# haptic-control.net
KiCad netlist of a schematic drawn in EAGLE
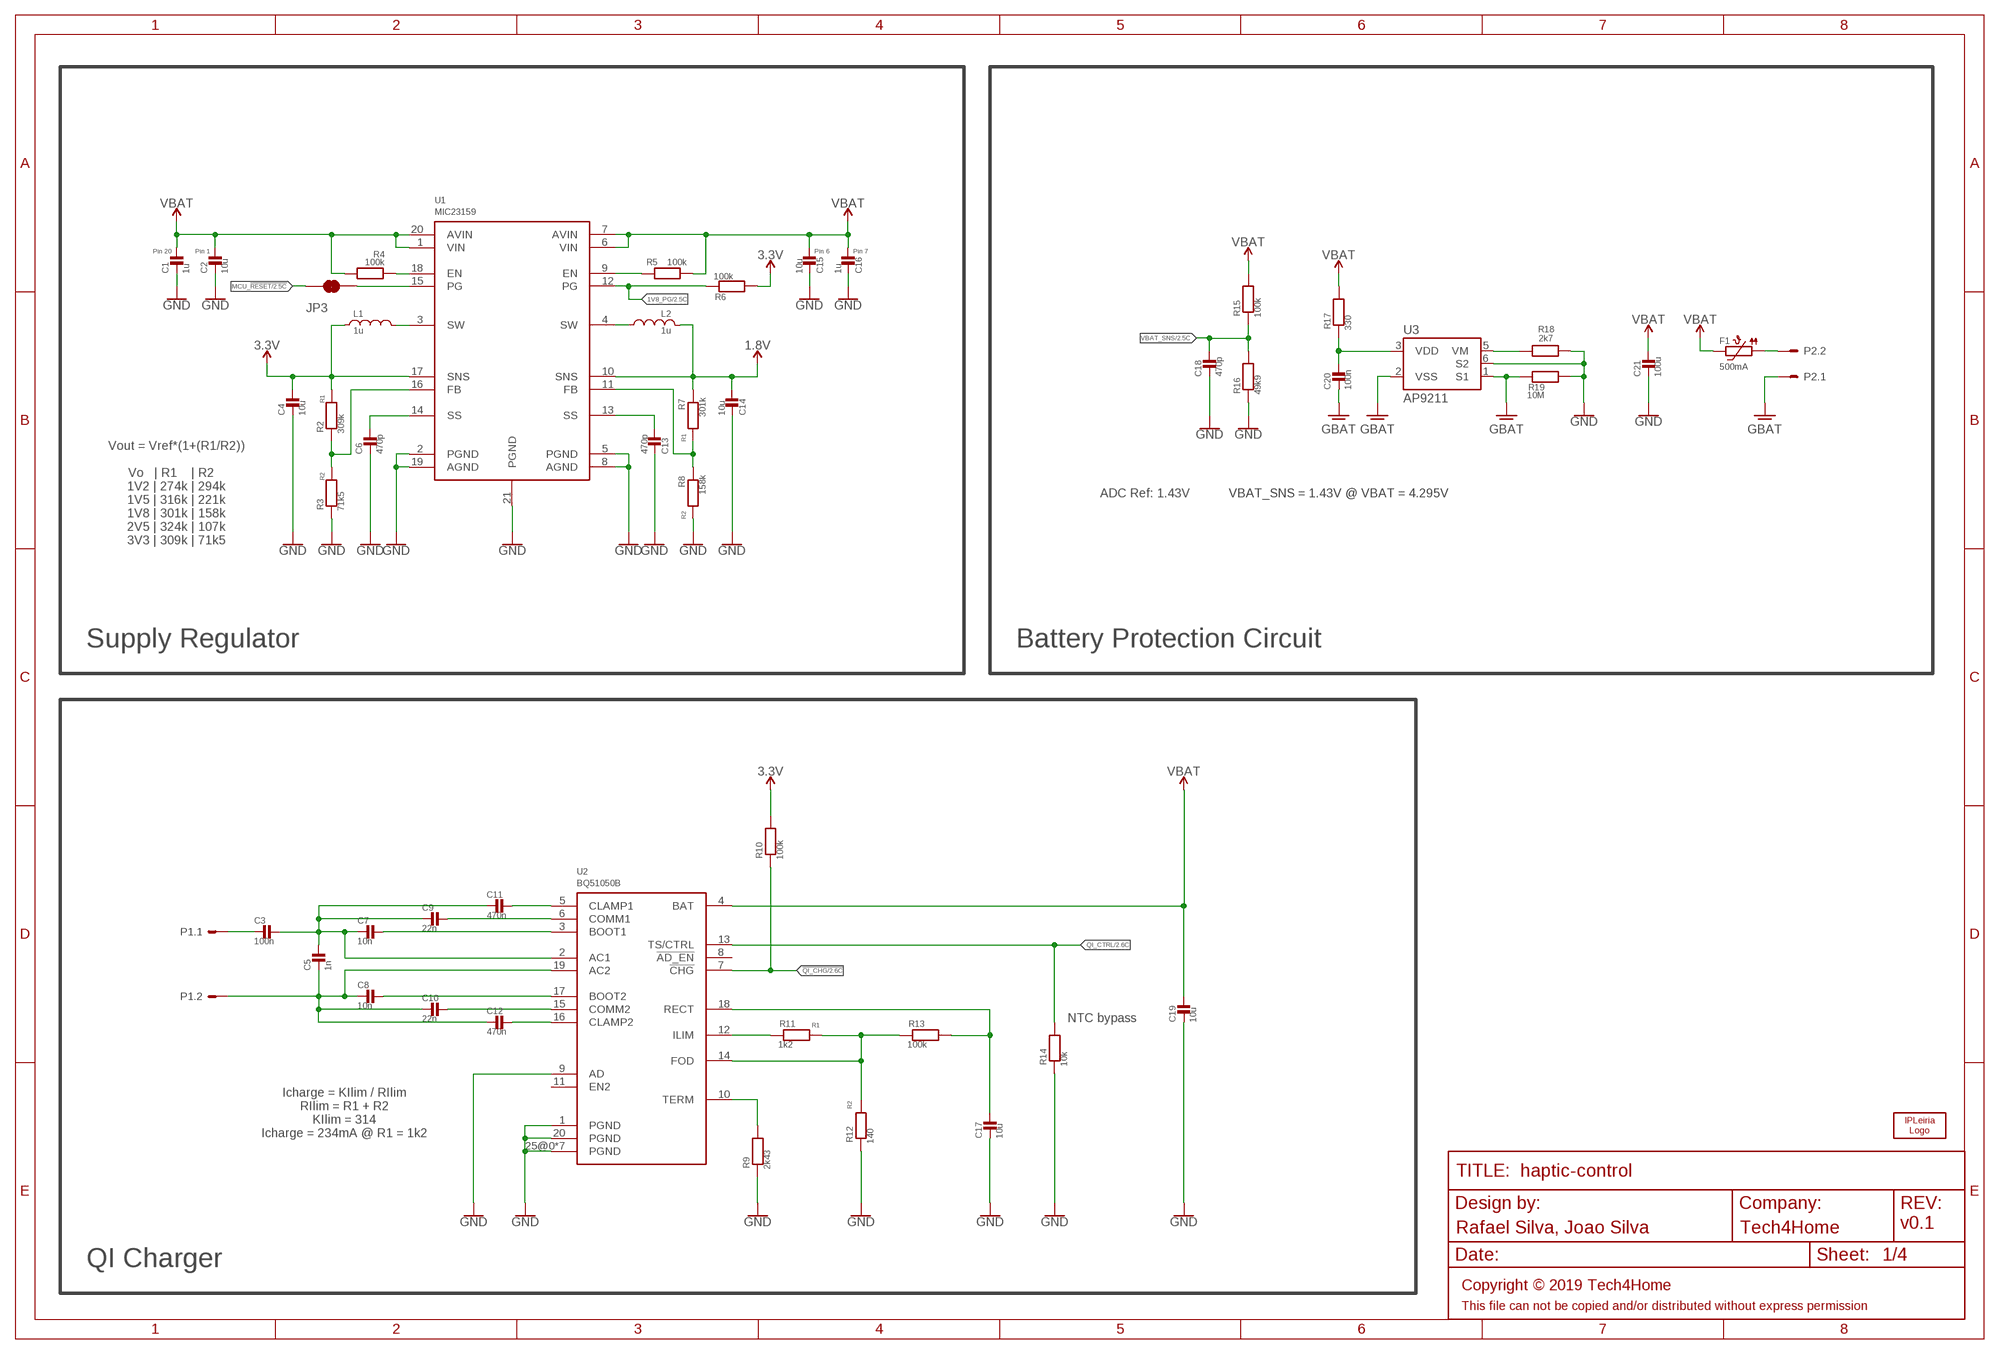
[diagram p0: schematic, sheet 1]
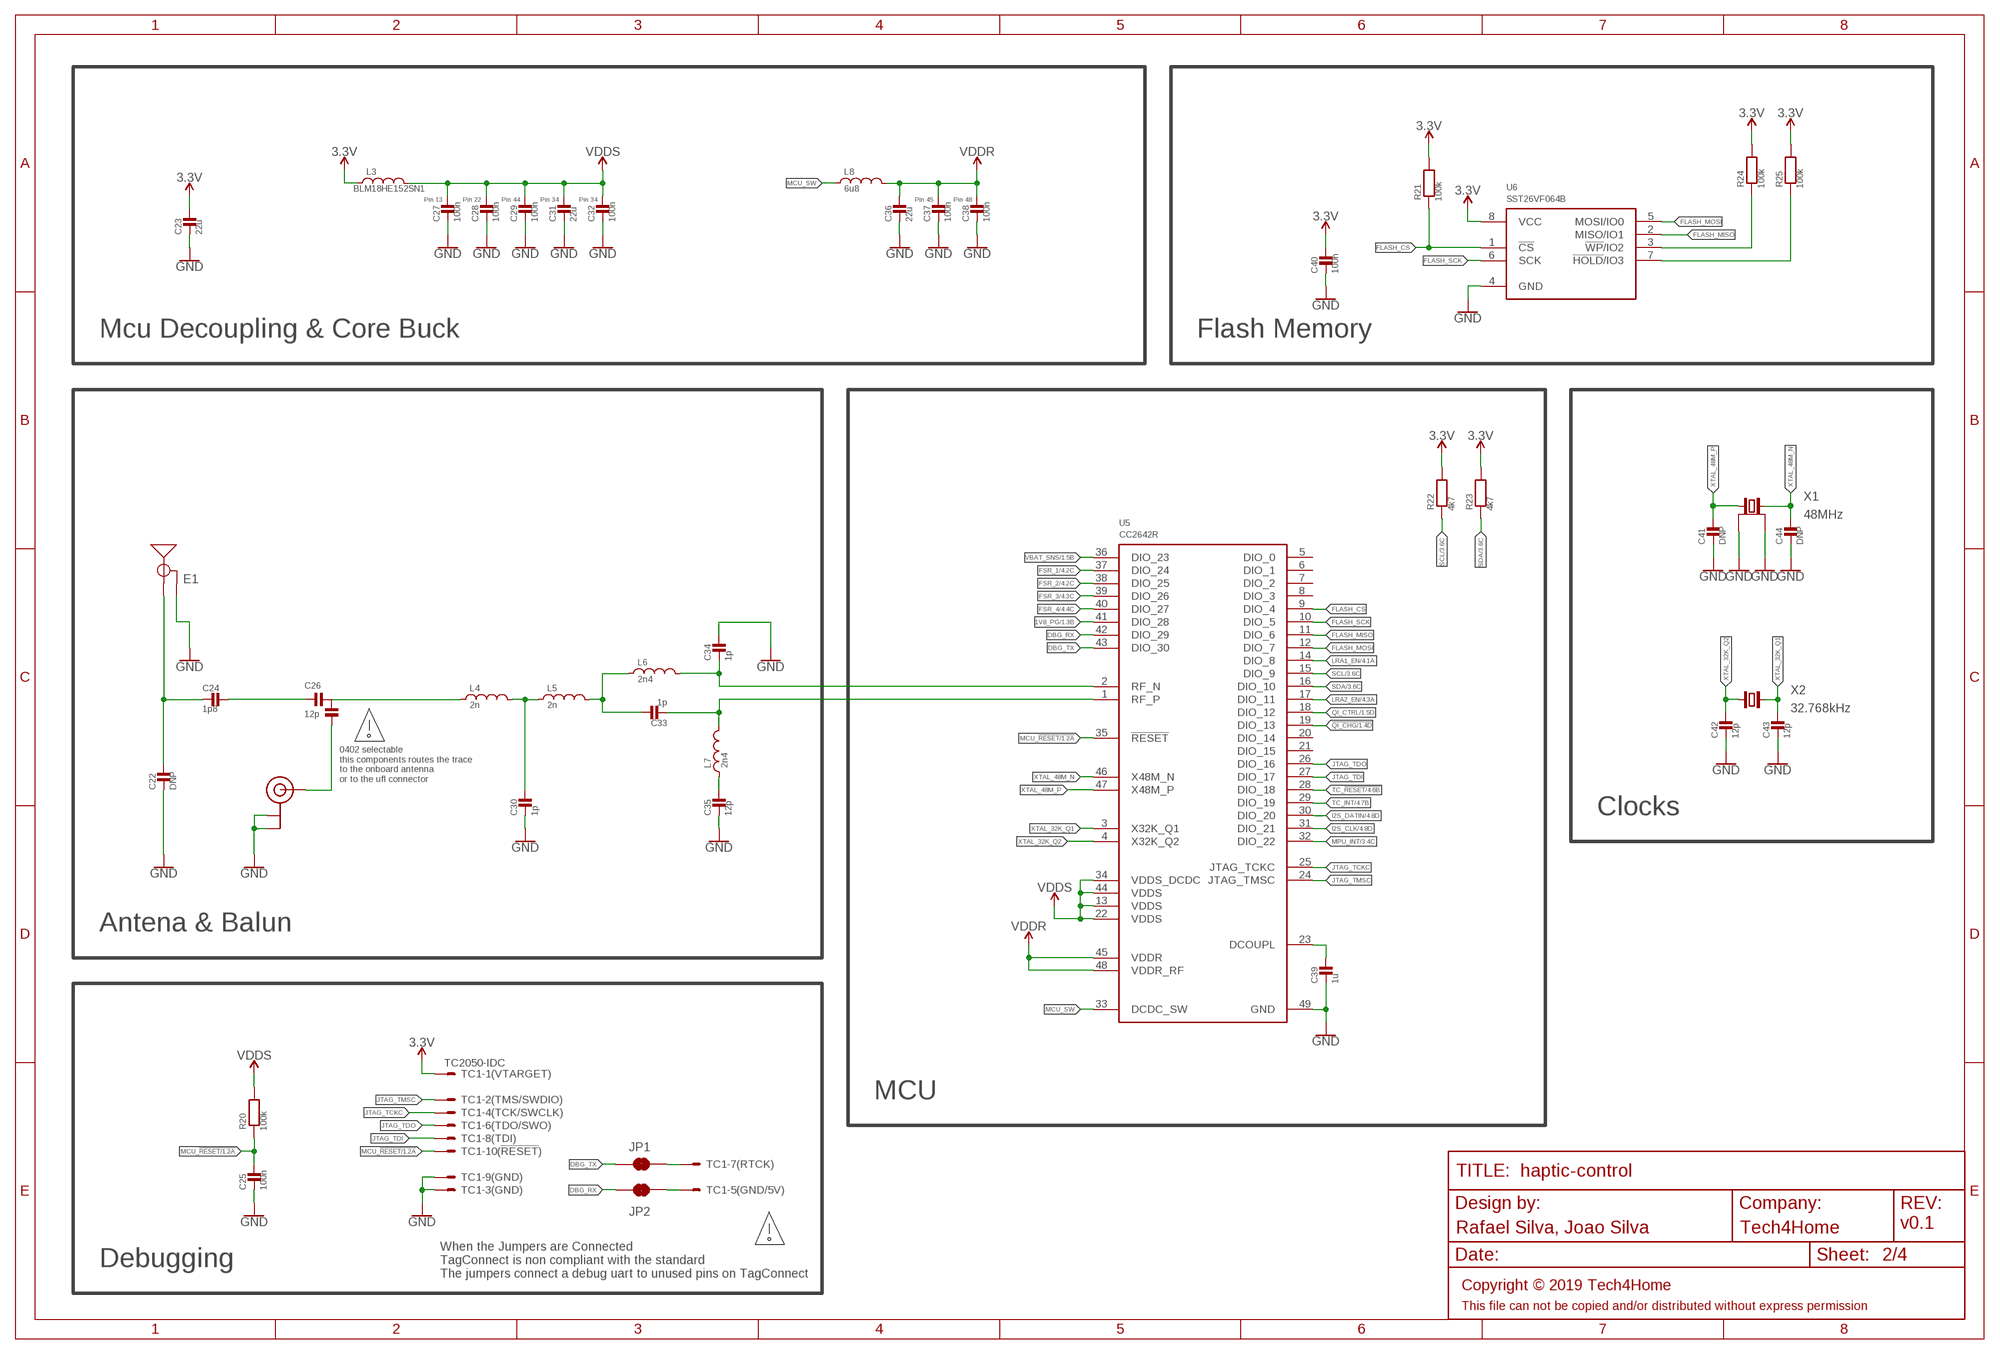
[diagram p1: schematic, sheet 2]
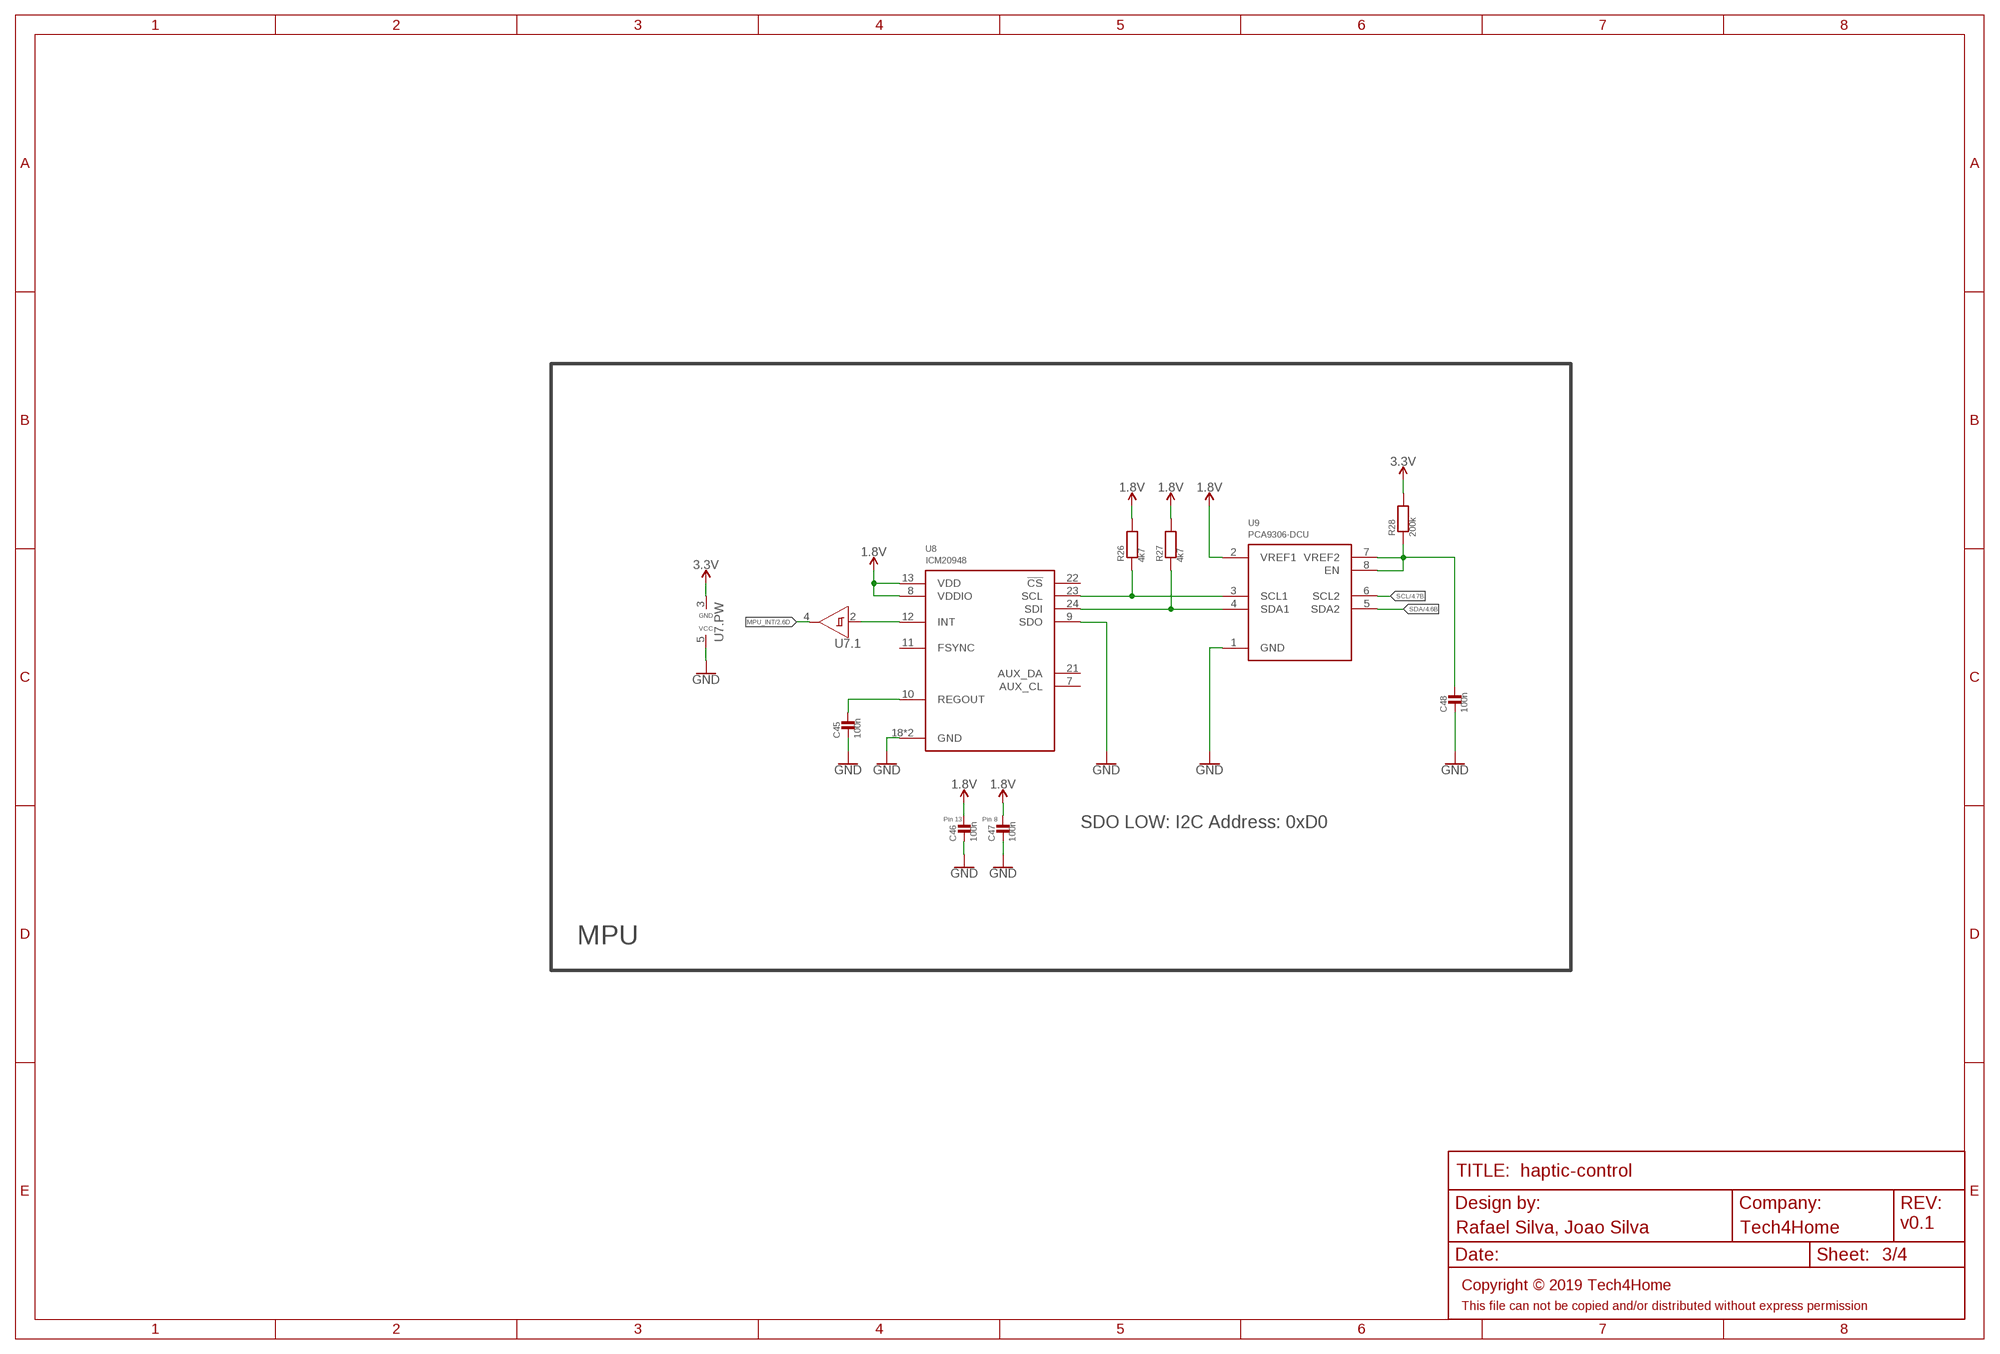
[diagram p2: schematic, sheet 3]
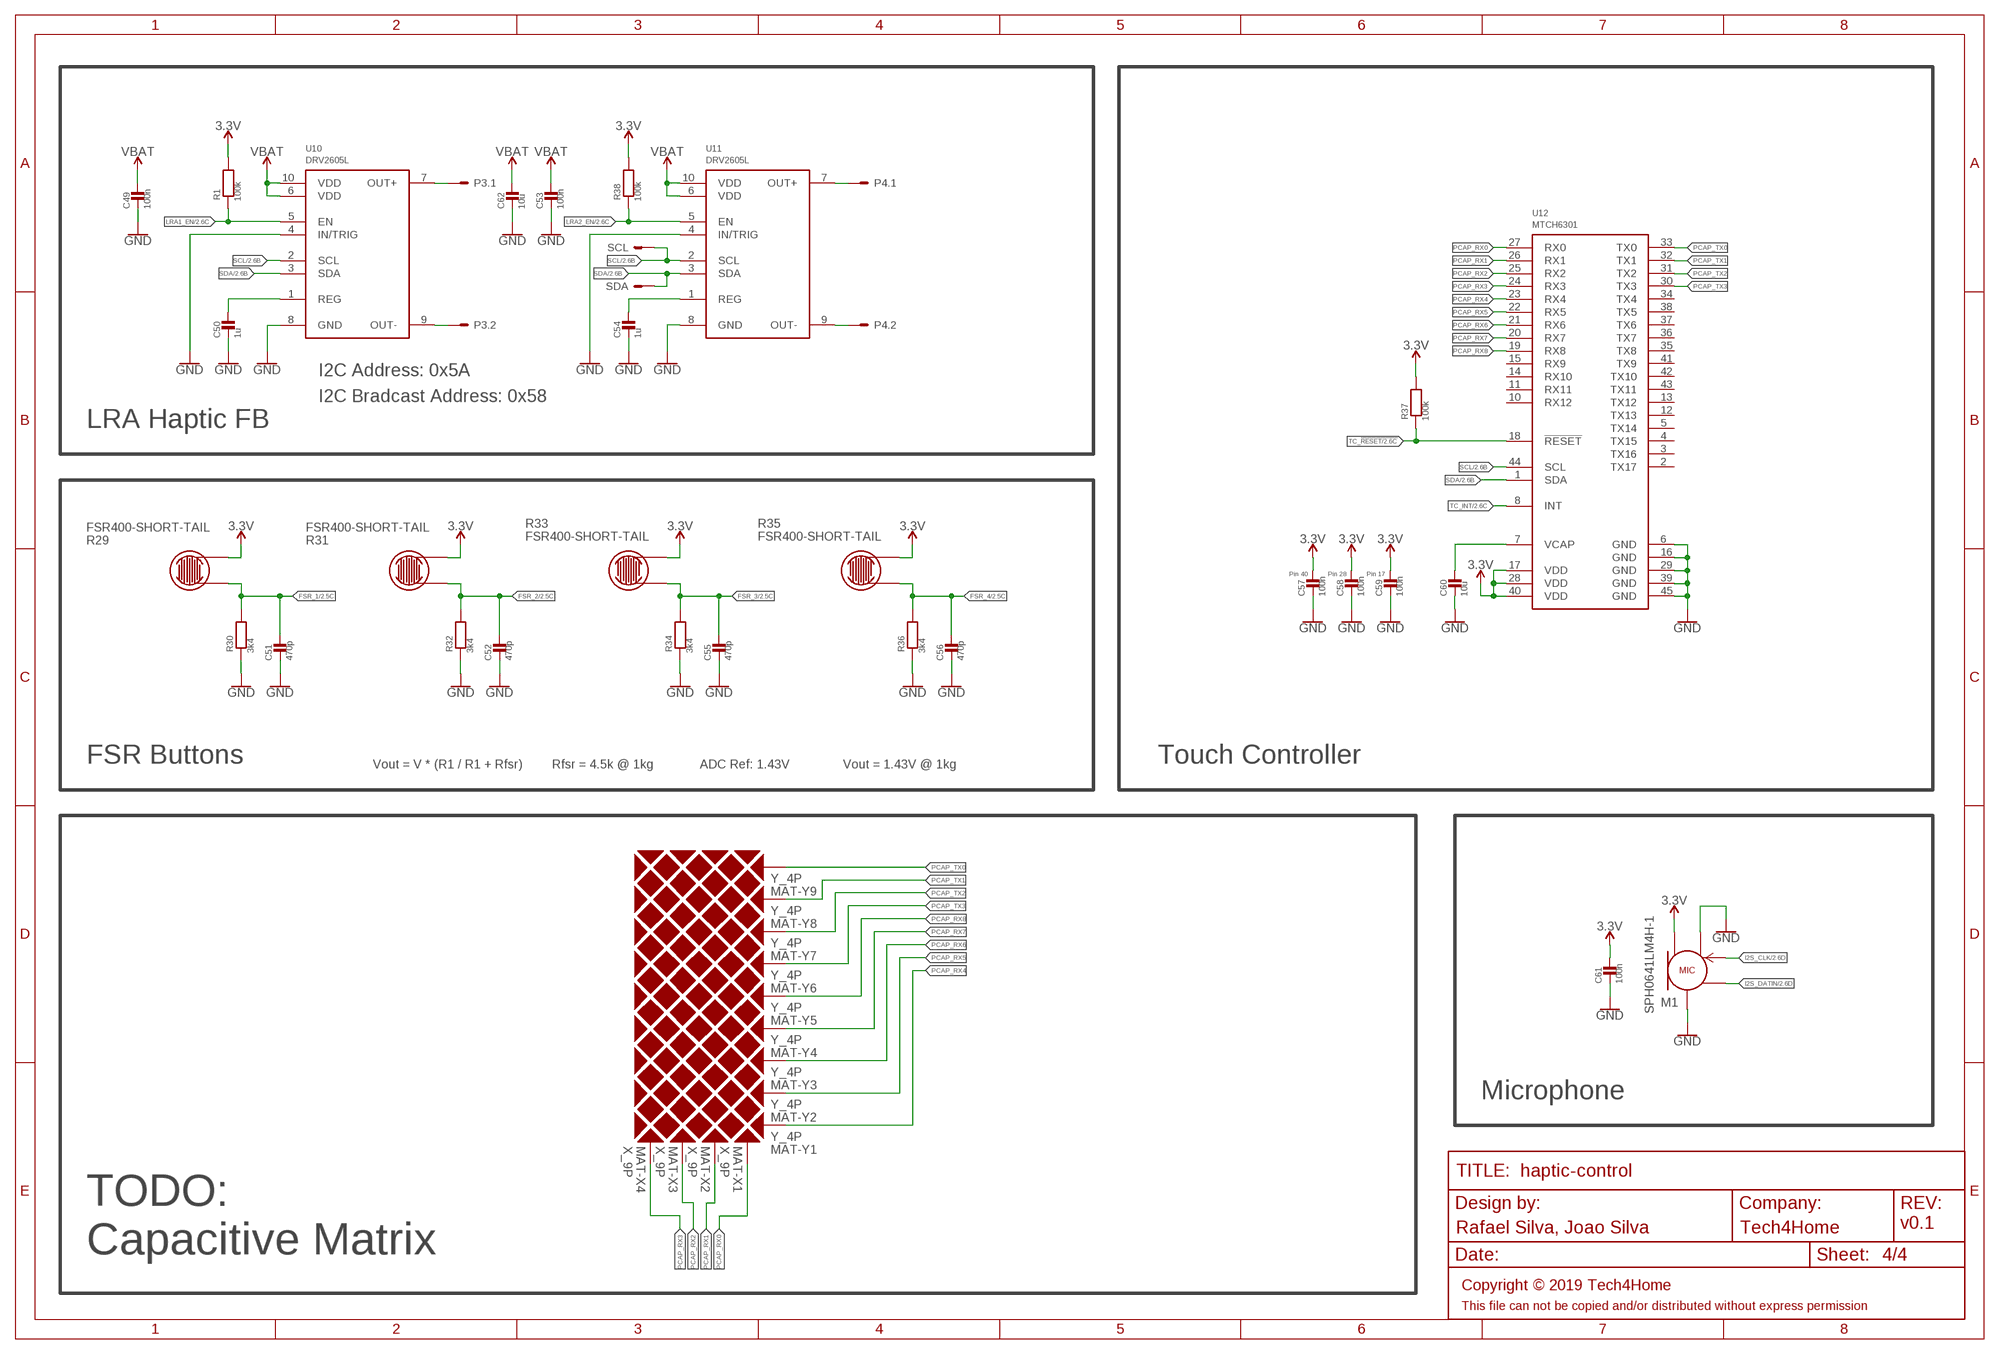
[diagram p3: schematic, sheet 4]

(export (version "E")
  (design (tool "Eeschema 10.0.6"))
  (components
    (comp (ref "C1")
      (value "1u")
      (footprint "eagle-import:0603_WAVE")
      (libsource (lib "eagle-import") (part "MLCC0603"))
    )
    (comp (ref "C2")
      (value "10u")
      (footprint "eagle-import:0603_WAVE")
      (libsource (lib "eagle-import") (part "MLCC0603"))
    )
    (comp (ref "C3")
      (value "100n")
      (footprint "eagle-import:_0402")
      (libsource (lib "eagle-import") (part "MLCC_0402"))
    )
    (comp (ref "C4")
      (value "10u")
      (footprint "eagle-import:0603_WAVE")
      (libsource (lib "eagle-import") (part "MLCC0603"))
    )
    (comp (ref "C5")
      (value "1n")
      (footprint "eagle-import:_0402")
      (libsource (lib "eagle-import") (part "MLCC_0402"))
    )
    (comp (ref "C6")
      (value "470p")
      (footprint "eagle-import:_0402")
      (libsource (lib "eagle-import") (part "MLCC_0402"))
    )
    (comp (ref "C7")
      (value "10n")
      (footprint "eagle-import:_0402")
      (libsource (lib "eagle-import") (part "MLCC_0402"))
    )
    (comp (ref "C8")
      (value "10n")
      (footprint "eagle-import:_0402")
      (libsource (lib "eagle-import") (part "MLCC_0402"))
    )
    (comp (ref "C9")
      (value "22n")
      (footprint "eagle-import:_0402")
      (libsource (lib "eagle-import") (part "MLCC_0402"))
    )
    (comp (ref "C10")
      (value "22n")
      (footprint "eagle-import:_0402")
      (libsource (lib "eagle-import") (part "MLCC_0402"))
    )
    (comp (ref "C11")
      (value "470n")
      (footprint "eagle-import:_0402")
      (libsource (lib "eagle-import") (part "MLCC_0402"))
    )
    (comp (ref "C12")
      (value "470n")
      (footprint "eagle-import:_0402")
      (libsource (lib "eagle-import") (part "MLCC_0402"))
    )
    (comp (ref "C13")
      (value "470p")
      (footprint "eagle-import:_0402")
      (libsource (lib "eagle-import") (part "MLCC_0402"))
    )
    (comp (ref "C14")
      (value "10u")
      (footprint "eagle-import:0603_WAVE")
      (libsource (lib "eagle-import") (part "MLCC0603"))
    )
    (comp (ref "C15")
      (value "10u")
      (footprint "eagle-import:0603_WAVE")
      (libsource (lib "eagle-import") (part "MLCC0603"))
    )
    (comp (ref "C16")
      (value "1u")
      (footprint "eagle-import:0603_WAVE")
      (libsource (lib "eagle-import") (part "MLCC0603"))
    )
    (comp (ref "C17")
      (value "10u")
      (footprint "eagle-import:0603_WAVE")
      (libsource (lib "eagle-import") (part "MLCC0603"))
    )
    (comp (ref "C18")
      (value "470p")
      (footprint "eagle-import:_0402")
      (libsource (lib "eagle-import") (part "MLCC_0402"))
    )
    (comp (ref "C19")
      (value "10u")
      (footprint "eagle-import:0603_WAVE")
      (libsource (lib "eagle-import") (part "MLCC0603"))
    )
    (comp (ref "C20")
      (value "100n")
      (footprint "eagle-import:_0402")
      (libsource (lib "eagle-import") (part "MLCC_0402"))
    )
    (comp (ref "C21")
      (value "100u")
      (footprint "eagle-import:_1206")
      (libsource (lib "eagle-import") (part "MLCC_1206"))
    )
    (comp (ref "F1")
      (value "500mA")
      (footprint "eagle-import:0805")
      (libsource (lib "eagle-import") (part "PTC0805"))
    )
    (comp (ref "JP3")
      (value "JUMPER-SMT_2_NC_TRACE_SILK")
      (footprint "eagle-import:SMT-JUMPER_2_NC_TRACE_SILK")
      (libsource (lib "eagle-import") (part "JUMPER-SMT_2_NC_TRACE_SILK"))
    )
    (comp (ref "L1")
      (value "1u")
      (footprint "eagle-import:_0806")
      (libsource (lib "eagle-import") (part "INDUCTOR_NC_0806"))
    )
    (comp (ref "L2")
      (value "1u")
      (footprint "eagle-import:_0806")
      (libsource (lib "eagle-import") (part "INDUCTOR_NC_0806"))
    )
    (comp (ref "LOGO1")
      (value "IPL-10MM")
      (footprint "eagle-import:IPL_10MM")
      (libsource (lib "eagle-import") (part "IPL-10MM"))
    )
    (comp (ref "P1")
      (value "2P-PAD_1X3.5")
      (footprint "eagle-import:PAD1X3_5MM-2P")
      (libsource (lib "eagle-import") (part "2P-PAD_1X3.5"))
    )
    (comp (ref "P2")
      (value "2P-PAD_1X3.5")
      (footprint "eagle-import:PAD1X3_5MM-2P")
      (libsource (lib "eagle-import") (part "2P-PAD_1X3.5"))
    )
    (comp (ref "R2")
      (value "309k")
      (footprint "eagle-import:_0402")
      (libsource (lib "eagle-import") (part "RESISTOR_0402"))
    )
    (comp (ref "R3")
      (value "71k5")
      (footprint "eagle-import:_0402")
      (libsource (lib "eagle-import") (part "RESISTOR_0402"))
    )
    (comp (ref "R4")
      (value "100k")
      (footprint "eagle-import:_0402")
      (libsource (lib "eagle-import") (part "RESISTOR_0402"))
    )
    (comp (ref "R5")
      (value "100k")
      (footprint "eagle-import:_0402")
      (libsource (lib "eagle-import") (part "RESISTOR_0402"))
    )
    (comp (ref "R6")
      (value "100k")
      (footprint "eagle-import:_0402")
      (libsource (lib "eagle-import") (part "RESISTOR_0402"))
    )
    (comp (ref "R7")
      (value "301k")
      (footprint "eagle-import:_0402")
      (libsource (lib "eagle-import") (part "RESISTOR_0402"))
    )
    (comp (ref "R8")
      (value "158k")
      (footprint "eagle-import:_0402")
      (libsource (lib "eagle-import") (part "RESISTOR_0402"))
    )
    (comp (ref "R9")
      (value "2k43")
      (footprint "eagle-import:_0402")
      (libsource (lib "eagle-import") (part "RESISTOR_0402"))
    )
    (comp (ref "R10")
      (value "100k")
      (footprint "eagle-import:_0402")
      (libsource (lib "eagle-import") (part "RESISTOR_0402"))
    )
    (comp (ref "R11")
      (value "1k2")
      (footprint "eagle-import:_0402")
      (libsource (lib "eagle-import") (part "RESISTOR_0402"))
    )
    (comp (ref "R12")
      (value "140")
      (footprint "eagle-import:_0402")
      (libsource (lib "eagle-import") (part "RESISTOR_0402"))
    )
    (comp (ref "R13")
      (value "100k")
      (footprint "eagle-import:_0402")
      (libsource (lib "eagle-import") (part "RESISTOR_0402"))
    )
    (comp (ref "R14")
      (value "10k")
      (footprint "eagle-import:_0402")
      (libsource (lib "eagle-import") (part "RESISTOR_0402"))
    )
    (comp (ref "R15")
      (value "100k")
      (footprint "eagle-import:_0402")
      (libsource (lib "eagle-import") (part "RESISTOR_0402"))
    )
    (comp (ref "R16")
      (value "49k9")
      (footprint "eagle-import:_0402")
      (libsource (lib "eagle-import") (part "RESISTOR_0402"))
    )
    (comp (ref "R17")
      (value "330")
      (footprint "eagle-import:_0402")
      (libsource (lib "eagle-import") (part "RESISTOR_0402"))
    )
    (comp (ref "R18")
      (value "2k7")
      (footprint "eagle-import:_0402")
      (libsource (lib "eagle-import") (part "RESISTOR_0402"))
    )
    (comp (ref "R19")
      (value "10M")
      (footprint "eagle-import:_0402")
      (libsource (lib "eagle-import") (part "RESISTOR_0402"))
    )
    (comp (ref "U1")
      (value "MIC23159")
      (footprint "eagle-import:VQFN20")
      (libsource (lib "eagle-import") (part "MIC23159"))
    )
    (comp (ref "U2")
      (value "BQ51050B")
      (footprint "eagle-import:VQFN20")
      (libsource (lib "eagle-import") (part "BQ51050B"))
    )
    (comp (ref "U3")
      (value "AP9211")
      (footprint "eagle-import:DFN2030-6")
      (libsource (lib "eagle-import") (part "AP9211"))
    )
    (comp (ref "C49")
      (value "100n")
      (footprint "eagle-import:_0402")
      (libsource (lib "eagle-import") (part "MLCC_0402"))
    )
    (comp (ref "C50")
      (value "1u")
      (footprint "eagle-import:0603_WAVE")
      (libsource (lib "eagle-import") (part "MLCC0603"))
    )
    (comp (ref "C51")
      (value "470p")
      (footprint "eagle-import:_0402")
      (libsource (lib "eagle-import") (part "MLCC_0402"))
    )
    (comp (ref "C52")
      (value "470p")
      (footprint "eagle-import:_0402")
      (libsource (lib "eagle-import") (part "MLCC_0402"))
    )
    (comp (ref "C53")
      (value "100n")
      (footprint "eagle-import:_0402")
      (libsource (lib "eagle-import") (part "MLCC_0402"))
    )
    (comp (ref "C54")
      (value "1u")
      (footprint "eagle-import:0603_WAVE")
      (libsource (lib "eagle-import") (part "MLCC0603"))
    )
    (comp (ref "C55")
      (value "470p")
      (footprint "eagle-import:_0402")
      (libsource (lib "eagle-import") (part "MLCC_0402"))
    )
    (comp (ref "C56")
      (value "470p")
      (footprint "eagle-import:_0402")
      (libsource (lib "eagle-import") (part "MLCC_0402"))
    )
    (comp (ref "C57")
      (value "100n")
      (footprint "eagle-import:_0402")
      (libsource (lib "eagle-import") (part "MLCC_0402"))
    )
    (comp (ref "C58")
      (value "100n")
      (footprint "eagle-import:_0402")
      (libsource (lib "eagle-import") (part "MLCC_0402"))
    )
    (comp (ref "C59")
      (value "100n")
      (footprint "eagle-import:_0402")
      (libsource (lib "eagle-import") (part "MLCC_0402"))
    )
    (comp (ref "C60")
      (value "10u")
      (footprint "eagle-import:0603_WAVE")
      (libsource (lib "eagle-import") (part "MLCC0603"))
    )
    (comp (ref "C61")
      (value "100n")
      (footprint "eagle-import:_0402")
      (libsource (lib "eagle-import") (part "MLCC_0402"))
    )
    (comp (ref "C62")
      (value "10u")
      (footprint "eagle-import:0603_WAVE")
      (libsource (lib "eagle-import") (part "MLCC0603"))
    )
    (comp (ref "M1")
      (value "SPH0641LM4H-1")
      (footprint "eagle-import:SPH0641LM4H-1")
      (libsource (lib "eagle-import") (part "SPH0641LM4H-1"))
    )
    (comp (ref "MAT-X1")
      (value "X_9P")
      (footprint "eagle-import:TOUCH_X_9P")
      (libsource (lib "eagle-import") (part "X_9P"))
    )
    (comp (ref "MAT-X2")
      (value "X_9P")
      (footprint "eagle-import:TOUCH_X_9P")
      (libsource (lib "eagle-import") (part "X_9P"))
    )
    (comp (ref "MAT-X3")
      (value "X_9P")
      (footprint "eagle-import:TOUCH_X_9P")
      (libsource (lib "eagle-import") (part "X_9P"))
    )
    (comp (ref "MAT-X4")
      (value "X_9P")
      (footprint "eagle-import:TOUCH_X_9P")
      (libsource (lib "eagle-import") (part "X_9P"))
    )
    (comp (ref "MAT-Y1")
      (value "Y_4P")
      (footprint "eagle-import:TOUCH_Y_4P")
      (libsource (lib "eagle-import") (part "Y_4P"))
    )
    (comp (ref "MAT-Y2")
      (value "Y_4P")
      (footprint "eagle-import:TOUCH_Y_4P")
      (libsource (lib "eagle-import") (part "Y_4P"))
    )
    (comp (ref "MAT-Y3")
      (value "Y_4P")
      (footprint "eagle-import:TOUCH_Y_4P")
      (libsource (lib "eagle-import") (part "Y_4P"))
    )
    (comp (ref "MAT-Y4")
      (value "Y_4P")
      (footprint "eagle-import:TOUCH_Y_4P")
      (libsource (lib "eagle-import") (part "Y_4P"))
    )
    (comp (ref "MAT-Y5")
      (value "Y_4P")
      (footprint "eagle-import:TOUCH_Y_4P")
      (libsource (lib "eagle-import") (part "Y_4P"))
    )
    (comp (ref "MAT-Y6")
      (value "Y_4P")
      (footprint "eagle-import:TOUCH_Y_4P")
      (libsource (lib "eagle-import") (part "Y_4P"))
    )
    (comp (ref "MAT-Y7")
      (value "Y_4P")
      (footprint "eagle-import:TOUCH_Y_4P")
      (libsource (lib "eagle-import") (part "Y_4P"))
    )
    (comp (ref "MAT-Y8")
      (value "Y_4P")
      (footprint "eagle-import:TOUCH_Y_4P")
      (libsource (lib "eagle-import") (part "Y_4P"))
    )
    (comp (ref "MAT-Y9")
      (value "Y_4P")
      (footprint "eagle-import:TOUCH_Y_4P")
      (libsource (lib "eagle-import") (part "Y_4P"))
    )
    (comp (ref "P3")
      (value "2P-PAD_1X3.5")
      (footprint "eagle-import:PAD1X3_5MM-2P")
      (libsource (lib "eagle-import") (part "2P-PAD_1X3.5"))
    )
    (comp (ref "P4")
      (value "2P-PAD_1X3.5")
      (footprint "eagle-import:PAD1X3_5MM-2P")
      (libsource (lib "eagle-import") (part "2P-PAD_1X3.5"))
    )
    (comp (ref "R1")
      (value "100k")
      (footprint "eagle-import:_0402")
      (libsource (lib "eagle-import") (part "RESISTOR_0402"))
    )
    (comp (ref "R29")
      (value "FSR400-SHORT-TAIL")
      (footprint "eagle-import:FSR400-SHORT-TAIL")
      (libsource (lib "eagle-import") (part "FSR400-SHORT-TAIL"))
    )
    (comp (ref "R30")
      (value "3k4")
      (footprint "eagle-import:_0402")
      (libsource (lib "eagle-import") (part "RESISTOR_0402"))
    )
    (comp (ref "R31")
      (value "FSR400-SHORT-TAIL")
      (footprint "eagle-import:FSR400-SHORT-TAIL")
      (libsource (lib "eagle-import") (part "FSR400-SHORT-TAIL"))
    )
    (comp (ref "R32")
      (value "3k4")
      (footprint "eagle-import:_0402")
      (libsource (lib "eagle-import") (part "RESISTOR_0402"))
    )
    (comp (ref "R33")
      (value "FSR400-SHORT-TAIL")
      (footprint "eagle-import:FSR400-SHORT-TAIL")
      (libsource (lib "eagle-import") (part "FSR400-SHORT-TAIL"))
    )
    (comp (ref "R34")
      (value "3k4")
      (footprint "eagle-import:_0402")
      (libsource (lib "eagle-import") (part "RESISTOR_0402"))
    )
    (comp (ref "R35")
      (value "FSR400-SHORT-TAIL")
      (footprint "eagle-import:FSR400-SHORT-TAIL")
      (libsource (lib "eagle-import") (part "FSR400-SHORT-TAIL"))
    )
    (comp (ref "R36")
      (value "3k4")
      (footprint "eagle-import:_0402")
      (libsource (lib "eagle-import") (part "RESISTOR_0402"))
    )
    (comp (ref "R37")
      (value "100k")
      (footprint "eagle-import:_0402")
      (libsource (lib "eagle-import") (part "RESISTOR_0402"))
    )
    (comp (ref "R38")
      (value "100k")
      (footprint "eagle-import:_0402")
      (libsource (lib "eagle-import") (part "RESISTOR_0402"))
    )
    (comp (ref "SCL")
      (value "TEST_POINT")
      (footprint "eagle-import:TEST_POINT")
      (libsource (lib "eagle-import") (part "TEST_POINT"))
    )
    (comp (ref "SDA")
      (value "TEST_POINT")
      (footprint "eagle-import:TEST_POINT")
      (libsource (lib "eagle-import") (part "TEST_POINT"))
    )
    (comp (ref "U10")
      (value "DRV2605L")
      (footprint "eagle-import:VSSOP10")
      (libsource (lib "eagle-import") (part "DRV2605L"))
    )
    (comp (ref "U11")
      (value "DRV2605L")
      (footprint "eagle-import:VSSOP10")
      (libsource (lib "eagle-import") (part "DRV2605L"))
    )
    (comp (ref "U12")
      (value "MTCH6301")
      (footprint "eagle-import:QFN44")
      (libsource (lib "eagle-import") (part "MTCH6301"))
    )
    (comp (ref "C45")
      (value "100n")
      (footprint "eagle-import:_0402")
      (libsource (lib "eagle-import") (part "MLCC_0402"))
    )
    (comp (ref "C46")
      (value "100n")
      (footprint "eagle-import:_0402")
      (libsource (lib "eagle-import") (part "MLCC_0402"))
    )
    (comp (ref "C47")
      (value "100n")
      (footprint "eagle-import:_0402")
      (libsource (lib "eagle-import") (part "MLCC_0402"))
    )
    (comp (ref "C48")
      (value "100n")
      (footprint "eagle-import:_0402")
      (libsource (lib "eagle-import") (part "MLCC_0402"))
    )
    (comp (ref "R26")
      (value "4k7")
      (footprint "eagle-import:_0402")
      (libsource (lib "eagle-import") (part "RESISTOR_0402"))
    )
    (comp (ref "R27")
      (value "4k7")
      (footprint "eagle-import:_0402")
      (libsource (lib "eagle-import") (part "RESISTOR_0402"))
    )
    (comp (ref "R28")
      (value "200k")
      (footprint "eagle-import:_0402")
      (libsource (lib "eagle-import") (part "RESISTOR_0402"))
    )
    (comp (ref "U7")
      (value "74LVC1G17")
      (footprint "eagle-import:SC70-5")
      (libsource (lib "eagle-import") (part "74LVC1G17"))
    )
    (comp (ref "U8")
      (value "ICM20948")
      (footprint "eagle-import:QFN20")
      (libsource (lib "eagle-import") (part "ICM20948"))
    )
    (comp (ref "U9")
      (value "PCA9306-DCU")
      (footprint "eagle-import:VSSOP8")
      (libsource (lib "eagle-import") (part "PCA9306-DCU"))
    )
    (comp (ref "A1")
      (value "U.FL")
      (footprint "eagle-import:U.FL")
      (libsource (lib "eagle-import") (part "U.FL"))
    )
    (comp (ref "C22")
      (value "DNP")
      (footprint "eagle-import:_0402")
      (libsource (lib "eagle-import") (part "MLCC_0402"))
    )
    (comp (ref "C23")
      (value "22u")
      (footprint "eagle-import:0603_WAVE")
      (libsource (lib "eagle-import") (part "MLCC0603"))
    )
    (comp (ref "C24")
      (value "1p8")
      (footprint "eagle-import:_0402")
      (libsource (lib "eagle-import") (part "MLCC_0402"))
    )
    (comp (ref "C25")
      (value "100n")
      (footprint "eagle-import:_0402")
      (libsource (lib "eagle-import") (part "MLCC_0402"))
    )
    (comp (ref "C26")
      (value "12p")
      (footprint "eagle-import:_0402_SEL")
      (libsource (lib "eagle-import") (part "MLCC_SEL"))
    )
    (comp (ref "C27")
      (value "100n")
      (footprint "eagle-import:_0402")
      (libsource (lib "eagle-import") (part "MLCC_0402"))
    )
    (comp (ref "C28")
      (value "100n")
      (footprint "eagle-import:_0402")
      (libsource (lib "eagle-import") (part "MLCC_0402"))
    )
    (comp (ref "C29")
      (value "100n")
      (footprint "eagle-import:_0402")
      (libsource (lib "eagle-import") (part "MLCC_0402"))
    )
    (comp (ref "C30")
      (value "1p")
      (footprint "eagle-import:_0402")
      (libsource (lib "eagle-import") (part "MLCC_0402"))
    )
    (comp (ref "C31")
      (value "22u")
      (footprint "eagle-import:0603_WAVE")
      (libsource (lib "eagle-import") (part "MLCC0603"))
    )
    (comp (ref "C32")
      (value "100n")
      (footprint "eagle-import:_0402")
      (libsource (lib "eagle-import") (part "MLCC_0402"))
    )
    (comp (ref "C33")
      (value "1p")
      (footprint "eagle-import:_0402")
      (libsource (lib "eagle-import") (part "MLCC_0402"))
    )
    (comp (ref "C34")
      (value "1p")
      (footprint "eagle-import:_0402")
      (libsource (lib "eagle-import") (part "MLCC_0402"))
    )
    (comp (ref "C35")
      (value "12p")
      (footprint "eagle-import:_0402")
      (libsource (lib "eagle-import") (part "MLCC_0402"))
    )
    (comp (ref "C36")
      (value "22u")
      (footprint "eagle-import:0603_WAVE")
      (libsource (lib "eagle-import") (part "MLCC0603"))
    )
    (comp (ref "C37")
      (value "100n")
      (footprint "eagle-import:_0402")
      (libsource (lib "eagle-import") (part "MLCC_0402"))
    )
    (comp (ref "C38")
      (value "100n")
      (footprint "eagle-import:_0402")
      (libsource (lib "eagle-import") (part "MLCC_0402"))
    )
    (comp (ref "C39")
      (value "1u")
      (footprint "eagle-import:0603_WAVE")
      (libsource (lib "eagle-import") (part "MLCC0603"))
    )
    (comp (ref "C40")
      (value "100n")
      (footprint "eagle-import:_0402")
      (libsource (lib "eagle-import") (part "MLCC_0402"))
    )
    (comp (ref "C41")
      (value "DNP")
      (footprint "eagle-import:_0402")
      (libsource (lib "eagle-import") (part "MLCC_0402"))
    )
    (comp (ref "C42")
      (value "12p")
      (footprint "eagle-import:_0402")
      (libsource (lib "eagle-import") (part "MLCC_0402"))
    )
    (comp (ref "C43")
      (value "12p")
      (footprint "eagle-import:_0402")
      (libsource (lib "eagle-import") (part "MLCC_0402"))
    )
    (comp (ref "C44")
      (value "DNP")
      (footprint "eagle-import:_0402")
      (libsource (lib "eagle-import") (part "MLCC_0402"))
    )
    (comp (ref "E1")
      (value "2.4GHZTRACE-15.2MM")
      (footprint "eagle-import:TRACE_ANTENNA_2.4GHZ_15.2MM")
      (libsource (lib "eagle-import") (part "2.4GHZTRACE-15.2MM"))
    )
    (comp (ref "JP1")
      (value "JUMPER-SMT_2_NC_TRACE_SILK")
      (footprint "eagle-import:SMT-JUMPER_2_NC_TRACE_SILK")
      (libsource (lib "eagle-import") (part "JUMPER-SMT_2_NC_TRACE_SILK"))
    )
    (comp (ref "JP2")
      (value "JUMPER-SMT_2_NC_TRACE_SILK")
      (footprint "eagle-import:SMT-JUMPER_2_NC_TRACE_SILK")
      (libsource (lib "eagle-import") (part "JUMPER-SMT_2_NC_TRACE_SILK"))
    )
    (comp (ref "L3")
      (value "BLM18HE152SN1")
      (footprint "eagle-import:_0603")
      (libsource (lib "eagle-import") (part "INDUCTOR_NC_0603"))
    )
    (comp (ref "L4")
      (value "2n")
      (footprint "eagle-import:_0402")
      (libsource (lib "eagle-import") (part "INDUCTOR_NC_0402"))
    )
    (comp (ref "L5")
      (value "2n")
      (footprint "eagle-import:_0402")
      (libsource (lib "eagle-import") (part "INDUCTOR_NC_0402"))
    )
    (comp (ref "L6")
      (value "2n4")
      (footprint "eagle-import:_0402")
      (libsource (lib "eagle-import") (part "INDUCTOR_NC_0402"))
    )
    (comp (ref "L7")
      (value "2n4")
      (footprint "eagle-import:_0402")
      (libsource (lib "eagle-import") (part "INDUCTOR_NC_0402"))
    )
    (comp (ref "L8")
      (value "6u8")
      (footprint "eagle-import:_0806")
      (libsource (lib "eagle-import") (part "INDUCTOR_NC_0806"))
    )
    (comp (ref "R20")
      (value "100k")
      (footprint "eagle-import:_0402")
      (libsource (lib "eagle-import") (part "RESISTOR_0402"))
    )
    (comp (ref "R21")
      (value "100k")
      (footprint "eagle-import:_0402")
      (libsource (lib "eagle-import") (part "RESISTOR_0402"))
    )
    (comp (ref "R22")
      (value "4k7")
      (footprint "eagle-import:_0402")
      (libsource (lib "eagle-import") (part "RESISTOR_0402"))
    )
    (comp (ref "R23")
      (value "4k7")
      (footprint "eagle-import:_0402")
      (libsource (lib "eagle-import") (part "RESISTOR_0402"))
    )
    (comp (ref "R24")
      (value "100k")
      (footprint "eagle-import:_0402")
      (libsource (lib "eagle-import") (part "RESISTOR_0402"))
    )
    (comp (ref "R25")
      (value "100k")
      (footprint "eagle-import:_0402")
      (libsource (lib "eagle-import") (part "RESISTOR_0402"))
    )
    (comp (ref "TC1")
      (value "TC2050-IDC")
      (footprint "eagle-import:TC2050-IDC")
      (libsource (lib "eagle-import") (part "TC2050-IDC"))
    )
    (comp (ref "U5")
      (value "CC2642R")
      (footprint "eagle-import:QFN48")
      (libsource (lib "eagle-import") (part "CC2642R"))
    )
    (comp (ref "U6")
      (value "SST26VF064B")
      (footprint "eagle-import:WSOIC8")
      (libsource (lib "eagle-import") (part "SST26VF064B"))
    )
    (comp (ref "X1")
      (value "48MHz")
      (footprint "eagle-import:4-SMD-3225")
      (libsource (lib "eagle-import") (part "CRYSTAL_4P"))
    )
    (comp (ref "X2")
      (value "32.768kHz")
      (footprint "eagle-import:2-SMD-3215")
      (libsource (lib "eagle-import") (part "CRYSTAL2-SMD-3215"))
    )
  )
  (nets
    (net (code "1") (name "1.8V") (class "Default")
      (node (ref "C14") (pin "P$1") (pinfunction "P$1_P$1") (pintype "bidirectional"))
      (node (ref "C46") (pin "1") (pinfunction "P$1_1") (pintype "bidirectional"))
      (node (ref "C47") (pin "1") (pinfunction "P$1_1") (pintype "bidirectional"))
      (node (ref "L2") (pin "1") (pinfunction "P$1_1") (pintype "bidirectional"))
      (node (ref "R26") (pin "2") (pinfunction "P$2_2") (pintype "bidirectional"))
      (node (ref "R27") (pin "2") (pinfunction "P$2_2") (pintype "bidirectional"))
      (node (ref "R7") (pin "1") (pinfunction "P$1_1") (pintype "bidirectional"))
      (node (ref "U1") (pin "10") (pinfunction "SNS_10") (pintype "bidirectional"))
      (node (ref "U8") (pin "13") (pinfunction "VDD_13") (pintype "bidirectional"))
      (node (ref "U8") (pin "8") (pinfunction "VDDIO_8") (pintype "bidirectional"))
      (node (ref "U9") (pin "2") (pinfunction "VREF1_2") (pintype "bidirectional"))
    )
    (net (code "2") (name "1V8_PG") (class "Default")
      (node (ref "R6") (pin "1") (pinfunction "P$1_1") (pintype "bidirectional"))
      (node (ref "U1") (pin "12") (pinfunction "PG_12") (pintype "bidirectional"))
      (node (ref "U5") (pin "41") (pinfunction "DIO_28_41") (pintype "bidirectional"))
    )
    (net (code "3") (name "3.3V") (class "Default")
      (node (ref "C23") (pin "P$1") (pinfunction "P$1_P$1") (pintype "bidirectional"))
      (node (ref "C4") (pin "P$1") (pinfunction "P$1_P$1") (pintype "bidirectional"))
      (node (ref "C40") (pin "1") (pinfunction "P$1_1") (pintype "bidirectional"))
      (node (ref "C57") (pin "1") (pinfunction "P$1_1") (pintype "bidirectional"))
      (node (ref "C58") (pin "1") (pinfunction "P$1_1") (pintype "bidirectional"))
      (node (ref "C59") (pin "1") (pinfunction "P$1_1") (pintype "bidirectional"))
      (node (ref "C61") (pin "1") (pinfunction "P$1_1") (pintype "bidirectional"))
      (node (ref "L1") (pin "1") (pinfunction "P$1_1") (pintype "bidirectional"))
      (node (ref "L3") (pin "1") (pinfunction "P$1_1") (pintype "bidirectional"))
      (node (ref "M1") (pin "5") (pinfunction "VCC_5") (pintype "passive"))
      (node (ref "R1") (pin "2") (pinfunction "P$2_2") (pintype "bidirectional"))
      (node (ref "R10") (pin "2") (pinfunction "P$2_2") (pintype "bidirectional"))
      (node (ref "R2") (pin "2") (pinfunction "P$2_2") (pintype "bidirectional"))
      (node (ref "R21") (pin "2") (pinfunction "P$2_2") (pintype "bidirectional"))
      (node (ref "R22") (pin "2") (pinfunction "P$2_2") (pintype "bidirectional"))
      (node (ref "R23") (pin "2") (pinfunction "P$2_2") (pintype "bidirectional"))
      (node (ref "R24") (pin "2") (pinfunction "P$2_2") (pintype "bidirectional"))
      (node (ref "R25") (pin "2") (pinfunction "P$2_2") (pintype "bidirectional"))
      (node (ref "R28") (pin "2") (pinfunction "P$2_2") (pintype "bidirectional"))
      (node (ref "R29") (pin "2") (pinfunction "2_2") (pintype "passive"))
      (node (ref "R31") (pin "2") (pinfunction "2_2") (pintype "passive"))
      (node (ref "R33") (pin "1") (pinfunction "1_1") (pintype "passive"))
      (node (ref "R35") (pin "1") (pinfunction "1_1") (pintype "passive"))
      (node (ref "R37") (pin "2") (pinfunction "P$2_2") (pintype "bidirectional"))
      (node (ref "R38") (pin "2") (pinfunction "P$2_2") (pintype "bidirectional"))
      (node (ref "R6") (pin "2") (pinfunction "P$2_2") (pintype "bidirectional"))
      (node (ref "TC1") (pin "1") (pinfunction "S_1") (pintype "passive"))
      (node (ref "U1") (pin "17") (pinfunction "SNS_17") (pintype "bidirectional"))
      (node (ref "U12") (pin "17") (pinfunction "VDD_17") (pintype "bidirectional"))
      (node (ref "U12") (pin "28") (pinfunction "VDD_28") (pintype "bidirectional"))
      (node (ref "U12") (pin "40") (pinfunction "VDD_40") (pintype "bidirectional"))
      (node (ref "U6") (pin "8") (pinfunction "VCC_8") (pintype "power_in"))
      (node (ref "U7") (pin "3") (pinfunction "GND_3") (pintype "bidirectional"))
    )
    (net (code "4") (name "DBG_RX") (class "Default")
      (node (ref "JP2") (pin "1") (pinfunction "1_1") (pintype "passive"))
      (node (ref "U5") (pin "42") (pinfunction "DIO_29_42") (pintype "bidirectional"))
    )
    (net (code "5") (name "DBG_TX") (class "Default")
      (node (ref "JP1") (pin "1") (pinfunction "1_1") (pintype "passive"))
      (node (ref "U5") (pin "43") (pinfunction "DIO_30_43") (pintype "bidirectional"))
    )
    (net (code "6") (name "FLASH_CS") (class "Default")
      (node (ref "R21") (pin "1") (pinfunction "P$1_1") (pintype "bidirectional"))
      (node (ref "U5") (pin "9") (pinfunction "DIO_4_9") (pintype "bidirectional"))
      (node (ref "U6") (pin "1") (pinfunction "~{CS}_1") (pintype "input"))
    )
    (net (code "7") (name "FLASH_MISO") (class "Default")
      (node (ref "U5") (pin "11") (pinfunction "DIO_6_11") (pintype "bidirectional"))
      (node (ref "U6") (pin "2") (pinfunction "MISO/IO1_2") (pintype "output"))
    )
    (net (code "8") (name "FLASH_MOSI") (class "Default")
      (node (ref "U5") (pin "12") (pinfunction "DIO_7_12") (pintype "bidirectional"))
      (node (ref "U6") (pin "5") (pinfunction "MOSI/IO0_5") (pintype "input"))
    )
    (net (code "9") (name "FLASH_SCK") (class "Default")
      (node (ref "U5") (pin "10") (pinfunction "DIO_5_10") (pintype "bidirectional"))
      (node (ref "U6") (pin "6") (pinfunction "SCK_6") (pintype "input"))
    )
    (net (code "10") (name "FSR_1") (class "Default")
      (node (ref "C51") (pin "1") (pinfunction "P$1_1") (pintype "bidirectional"))
      (node (ref "R29") (pin "1") (pinfunction "1_1") (pintype "passive"))
      (node (ref "R30") (pin "2") (pinfunction "P$2_2") (pintype "bidirectional"))
      (node (ref "U5") (pin "37") (pinfunction "DIO_24_37") (pintype "bidirectional"))
    )
    (net (code "11") (name "FSR_2") (class "Default")
      (node (ref "C52") (pin "1") (pinfunction "P$1_1") (pintype "bidirectional"))
      (node (ref "R31") (pin "1") (pinfunction "1_1") (pintype "passive"))
      (node (ref "R32") (pin "2") (pinfunction "P$2_2") (pintype "bidirectional"))
      (node (ref "U5") (pin "38") (pinfunction "DIO_25_38") (pintype "bidirectional"))
    )
    (net (code "12") (name "FSR_3") (class "Default")
      (node (ref "C55") (pin "1") (pinfunction "P$1_1") (pintype "bidirectional"))
      (node (ref "R33") (pin "2") (pinfunction "2_2") (pintype "passive"))
      (node (ref "R34") (pin "2") (pinfunction "P$2_2") (pintype "bidirectional"))
      (node (ref "U5") (pin "39") (pinfunction "DIO_26_39") (pintype "bidirectional"))
    )
    (net (code "13") (name "FSR_4") (class "Default")
      (node (ref "C56") (pin "1") (pinfunction "P$1_1") (pintype "bidirectional"))
      (node (ref "R35") (pin "2") (pinfunction "2_2") (pintype "passive"))
      (node (ref "R36") (pin "2") (pinfunction "P$2_2") (pintype "bidirectional"))
      (node (ref "U5") (pin "40") (pinfunction "DIO_27_40") (pintype "bidirectional"))
    )
    (net (code "14") (name "GBAT") (class "Default")
      (node (ref "C20") (pin "2") (pinfunction "P$2_2") (pintype "bidirectional"))
      (node (ref "P2") (pin "1") (pinfunction "S_1") (pintype "passive"))
      (node (ref "R19") (pin "1") (pinfunction "P$1_1") (pintype "bidirectional"))
      (node (ref "U3") (pin "1") (pinfunction "S1_1") (pintype "bidirectional"))
      (node (ref "U3") (pin "2") (pinfunction "VSS_2") (pintype "bidirectional"))
    )
    (net (code "15") (name "GND") (class "Default")
      (node (ref "A1") (pin "P$1") (pinfunction "GND_P$1") (pintype "bidirectional"))
      (node (ref "A1") (pin "P$2") (pinfunction "GND_P$2") (pintype "bidirectional"))
      (node (ref "C1") (pin "P$2") (pinfunction "P$2_P$2") (pintype "bidirectional"))
      (node (ref "C13") (pin "2") (pinfunction "P$2_2") (pintype "bidirectional"))
      (node (ref "C14") (pin "P$2") (pinfunction "P$2_P$2") (pintype "bidirectional"))
      (node (ref "C15") (pin "P$2") (pinfunction "P$2_P$2") (pintype "bidirectional"))
      (node (ref "C16") (pin "P$2") (pinfunction "P$2_P$2") (pintype "bidirectional"))
      (node (ref "C17") (pin "P$2") (pinfunction "P$2_P$2") (pintype "bidirectional"))
      (node (ref "C18") (pin "2") (pinfunction "P$2_2") (pintype "bidirectional"))
      (node (ref "C19") (pin "P$2") (pinfunction "P$2_P$2") (pintype "bidirectional"))
      (node (ref "C2") (pin "P$2") (pinfunction "P$2_P$2") (pintype "bidirectional"))
      (node (ref "C21") (pin "2") (pinfunction "P$2_2") (pintype "bidirectional"))
      (node (ref "C22") (pin "2") (pinfunction "P$2_2") (pintype "bidirectional"))
      (node (ref "C23") (pin "P$2") (pinfunction "P$2_P$2") (pintype "bidirectional"))
      (node (ref "C25") (pin "2") (pinfunction "P$2_2") (pintype "bidirectional"))
      (node (ref "C27") (pin "2") (pinfunction "P$2_2") (pintype "bidirectional"))
      (node (ref "C28") (pin "2") (pinfunction "P$2_2") (pintype "bidirectional"))
      (node (ref "C29") (pin "2") (pinfunction "P$2_2") (pintype "bidirectional"))
      (node (ref "C30") (pin "2") (pinfunction "P$2_2") (pintype "bidirectional"))
      (node (ref "C31") (pin "P$2") (pinfunction "P$2_P$2") (pintype "bidirectional"))
      (node (ref "C32") (pin "2") (pinfunction "P$2_2") (pintype "bidirectional"))
      (node (ref "C34") (pin "1") (pinfunction "P$1_1") (pintype "bidirectional"))
      (node (ref "C35") (pin "2") (pinfunction "P$2_2") (pintype "bidirectional"))
      (node (ref "C36") (pin "P$2") (pinfunction "P$2_P$2") (pintype "bidirectional"))
      (node (ref "C37") (pin "2") (pinfunction "P$2_2") (pintype "bidirectional"))
      (node (ref "C38") (pin "2") (pinfunction "P$2_2") (pintype "bidirectional"))
      (node (ref "C39") (pin "P$2") (pinfunction "P$2_P$2") (pintype "bidirectional"))
      (node (ref "C4") (pin "P$2") (pinfunction "P$2_P$2") (pintype "bidirectional"))
      (node (ref "C40") (pin "2") (pinfunction "P$2_2") (pintype "bidirectional"))
      (node (ref "C41") (pin "2") (pinfunction "P$2_2") (pintype "bidirectional"))
      (node (ref "C42") (pin "2") (pinfunction "P$2_2") (pintype "bidirectional"))
      (node (ref "C43") (pin "2") (pinfunction "P$2_2") (pintype "bidirectional"))
      (node (ref "C44") (pin "2") (pinfunction "P$2_2") (pintype "bidirectional"))
      (node (ref "C45") (pin "2") (pinfunction "P$2_2") (pintype "bidirectional"))
      (node (ref "C46") (pin "2") (pinfunction "P$2_2") (pintype "bidirectional"))
      (node (ref "C47") (pin "2") (pinfunction "P$2_2") (pintype "bidirectional"))
      (node (ref "C48") (pin "2") (pinfunction "P$2_2") (pintype "bidirectional"))
      (node (ref "C49") (pin "2") (pinfunction "P$2_2") (pintype "bidirectional"))
      (node (ref "C50") (pin "P$2") (pinfunction "P$2_P$2") (pintype "bidirectional"))
      (node (ref "C51") (pin "2") (pinfunction "P$2_2") (pintype "bidirectional"))
      (node (ref "C52") (pin "2") (pinfunction "P$2_2") (pintype "bidirectional"))
      (node (ref "C53") (pin "2") (pinfunction "P$2_2") (pintype "bidirectional"))
      (node (ref "C54") (pin "P$2") (pinfunction "P$2_P$2") (pintype "bidirectional"))
      (node (ref "C55") (pin "2") (pinfunction "P$2_2") (pintype "bidirectional"))
      (node (ref "C56") (pin "2") (pinfunction "P$2_2") (pintype "bidirectional"))
      (node (ref "C57") (pin "2") (pinfunction "P$2_2") (pintype "bidirectional"))
      (node (ref "C58") (pin "2") (pinfunction "P$2_2") (pintype "bidirectional"))
      (node (ref "C59") (pin "2") (pinfunction "P$2_2") (pintype "bidirectional"))
      (node (ref "C6") (pin "2") (pinfunction "P$2_2") (pintype "bidirectional"))
      (node (ref "C60") (pin "P$2") (pinfunction "P$2_P$2") (pintype "bidirectional"))
      (node (ref "C61") (pin "2") (pinfunction "P$2_2") (pintype "bidirectional"))
      (node (ref "C62") (pin "P$2") (pinfunction "P$2_P$2") (pintype "bidirectional"))
      (node (ref "E1") (pin "GND") (pinfunction "GND_GND") (pintype "bidirectional"))
      (node (ref "M1") (pin "2") (pinfunction "SEL_2") (pintype "passive"))
      (node (ref "M1") (pin "3") (pinfunction "GND_3") (pintype "passive"))
      (node (ref "R12") (pin "1") (pinfunction "P$1_1") (pintype "bidirectional"))
      (node (ref "R14") (pin "1") (pinfunction "P$1_1") (pintype "bidirectional"))
      (node (ref "R16") (pin "1") (pinfunction "P$1_1") (pintype "bidirectional"))
      (node (ref "R18") (pin "1") (pinfunction "P$1_1") (pintype "bidirectional"))
      (node (ref "R19") (pin "2") (pinfunction "P$2_2") (pintype "bidirectional"))
      (node (ref "R3") (pin "1") (pinfunction "P$1_1") (pintype "bidirectional"))
      (node (ref "R30") (pin "1") (pinfunction "P$1_1") (pintype "bidirectional"))
      (node (ref "R32") (pin "1") (pinfunction "P$1_1") (pintype "bidirectional"))
      (node (ref "R34") (pin "1") (pinfunction "P$1_1") (pintype "bidirectional"))
      (node (ref "R36") (pin "1") (pinfunction "P$1_1") (pintype "bidirectional"))
      (node (ref "R8") (pin "2") (pinfunction "P$2_2") (pintype "bidirectional"))
      (node (ref "R9") (pin "1") (pinfunction "P$1_1") (pintype "bidirectional"))
      (node (ref "TC1") (pin "3") (pinfunction "S_3") (pintype "passive"))
      (node (ref "TC1") (pin "9") (pinfunction "S_9") (pintype "passive"))
      (node (ref "U1") (pin "19") (pinfunction "AGND_19") (pintype "bidirectional"))
      (node (ref "U1") (pin "2") (pinfunction "PGND_2") (pintype "bidirectional"))
      (node (ref "U1") (pin "21") (pinfunction "PGND_21") (pintype "bidirectional"))
      (node (ref "U1") (pin "5") (pinfunction "PGND_5") (pintype "bidirectional"))
      (node (ref "U1") (pin "8") (pinfunction "AGND_8") (pintype "bidirectional"))
      (node (ref "U10") (pin "4") (pinfunction "IN/TRIG_4") (pintype "bidirectional"))
      (node (ref "U10") (pin "8") (pinfunction "GND_8") (pintype "bidirectional"))
      (node (ref "U11") (pin "4") (pinfunction "IN/TRIG_4") (pintype "bidirectional"))
      (node (ref "U11") (pin "8") (pinfunction "GND_8") (pintype "bidirectional"))
      (node (ref "U12") (pin "16") (pinfunction "GND_16") (pintype "bidirectional"))
      (node (ref "U12") (pin "29") (pinfunction "GND_29") (pintype "bidirectional"))
      (node (ref "U12") (pin "39") (pinfunction "GND_39") (pintype "bidirectional"))
      (node (ref "U12") (pin "45") (pinfunction "GND_45") (pintype "bidirectional"))
      (node (ref "U12") (pin "6") (pinfunction "GND_6") (pintype "bidirectional"))
      (node (ref "U2") (pin "1") (pinfunction "PGND_1") (pintype "bidirectional"))
      (node (ref "U2") (pin "20") (pinfunction "PGND_20") (pintype "bidirectional"))
      (node (ref "U2") (pin "25@0") (pinfunction "PGND_25@0") (pintype "bidirectional"))
      (node (ref "U2") (pin "25@1") (pinfunction "PGND_25@1") (pintype "bidirectional"))
      (node (ref "U2") (pin "25@2") (pinfunction "PGND_25@2") (pintype "bidirectional"))
      (node (ref "U2") (pin "25@3") (pinfunction "PGND_25@3") (pintype "bidirectional"))
      (node (ref "U2") (pin "25@4") (pinfunction "PGND_25@4") (pintype "bidirectional"))
      (node (ref "U2") (pin "25@5") (pinfunction "PGND_25@5") (pintype "bidirectional"))
      (node (ref "U2") (pin "25@6") (pinfunction "PGND_25@6") (pintype "bidirectional"))
      (node (ref "U2") (pin "9") (pinfunction "AD_9") (pintype "bidirectional"))
      (node (ref "U3") (pin "6") (pinfunction "S2_6") (pintype "bidirectional"))
      (node (ref "U5") (pin "49") (pinfunction "GND_49") (pintype "bidirectional"))
      (node (ref "U6") (pin "4") (pinfunction "GND_4") (pintype "power_in"))
      (node (ref "U7") (pin "5") (pinfunction "VCC_5") (pintype "bidirectional"))
      (node (ref "U8") (pin "18") (pinfunction "GND_18") (pintype "bidirectional"))
      (node (ref "U8") (pin "20") (pinfunction "GND_20") (pintype "bidirectional"))
      (node (ref "U8") (pin "9") (pinfunction "SDO_9") (pintype "bidirectional"))
      (node (ref "U9") (pin "1") (pinfunction "GND_1") (pintype "bidirectional"))
      (node (ref "X1") (pin "2") (pinfunction "GND_2") (pintype "passive"))
      (node (ref "X1") (pin "4") (pinfunction "GND_4") (pintype "passive"))
    )
    (net (code "16") (name "I2S_CLK") (class "Default")
      (node (ref "M1") (pin "4") (pinfunction "CLK_4") (pintype "passive"))
      (node (ref "U5") (pin "31") (pinfunction "DIO_21_31") (pintype "bidirectional"))
    )
    (net (code "17") (name "I2S_DATIN") (class "Default")
      (node (ref "M1") (pin "1") (pinfunction "DAT_1") (pintype "passive"))
      (node (ref "U5") (pin "30") (pinfunction "DIO_20_30") (pintype "bidirectional"))
    )
    (net (code "18") (name "JTAG_TCKC") (class "Default")
      (node (ref "TC1") (pin "4") (pinfunction "S_4") (pintype "passive"))
      (node (ref "U5") (pin "25") (pinfunction "JTAG_TCKC_25") (pintype "bidirectional"))
    )
    (net (code "19") (name "JTAG_TDI") (class "Default")
      (node (ref "TC1") (pin "8") (pinfunction "S_8") (pintype "passive"))
      (node (ref "U5") (pin "27") (pinfunction "DIO_17_27") (pintype "bidirectional"))
    )
    (net (code "20") (name "JTAG_TDO") (class "Default")
      (node (ref "TC1") (pin "6") (pinfunction "S_6") (pintype "passive"))
      (node (ref "U5") (pin "26") (pinfunction "DIO_16_26") (pintype "bidirectional"))
    )
    (net (code "21") (name "JTAG_TMSC") (class "Default")
      (node (ref "TC1") (pin "2") (pinfunction "S_2") (pintype "passive"))
      (node (ref "U5") (pin "24") (pinfunction "JTAG_TMSC_24") (pintype "bidirectional"))
    )
    (net (code "22") (name "LRA1_EN") (class "Default")
      (node (ref "R1") (pin "1") (pinfunction "P$1_1") (pintype "bidirectional"))
      (node (ref "U10") (pin "5") (pinfunction "EN_5") (pintype "bidirectional"))
      (node (ref "U5") (pin "14") (pinfunction "DIO_8_14") (pintype "bidirectional"))
    )
    (net (code "23") (name "LRA2_EN") (class "Default")
      (node (ref "R38") (pin "1") (pinfunction "P$1_1") (pintype "bidirectional"))
      (node (ref "U11") (pin "5") (pinfunction "EN_5") (pintype "bidirectional"))
      (node (ref "U5") (pin "17") (pinfunction "DIO_11_17") (pintype "bidirectional"))
    )
    (net (code "24") (name "MCU_SW") (class "Default")
      (node (ref "L8") (pin "1") (pinfunction "P$1_1") (pintype "bidirectional"))
      (node (ref "U5") (pin "33") (pinfunction "DCDC_SW_33") (pintype "bidirectional"))
    )
    (net (code "25") (name "MCU_~{RESET}") (class "Default")
      (node (ref "C25") (pin "1") (pinfunction "P$1_1") (pintype "bidirectional"))
      (node (ref "JP3") (pin "1") (pinfunction "1_1") (pintype "passive"))
      (node (ref "R20") (pin "1") (pinfunction "P$1_1") (pintype "bidirectional"))
      (node (ref "TC1") (pin "10") (pinfunction "S_10") (pintype "passive"))
      (node (ref "U5") (pin "35") (pinfunction "~{RESET}_35") (pintype "bidirectional"))
    )
    (net (code "26") (name "MPU_INT") (class "Default")
      (node (ref "U5") (pin "32") (pinfunction "DIO_22_32") (pintype "bidirectional"))
      (node (ref "U7") (pin "4") (pinfunction "Y_4") (pintype "output"))
    )
    (net (code "27") (name "Net-(A1-SIGNAL)") (class "Default")
      (node (ref "A1") (pin "P$3") (pinfunction "SIGNAL_P$3") (pintype "bidirectional"))
      (node (ref "C26") (pin "2") (pinfunction "O1_2") (pintype "bidirectional"))
    )
    (net (code "28") (name "Net-(C3-P$2)") (class "Default")
      (node (ref "C3") (pin "2") (pinfunction "P$2_2") (pintype "bidirectional"))
      (node (ref "P1") (pin "1") (pinfunction "S_1") (pintype "passive"))
    )
    (net (code "29") (name "Net-(C6-P$1)") (class "Default")
      (node (ref "C6") (pin "1") (pinfunction "P$1_1") (pintype "bidirectional"))
      (node (ref "U1") (pin "14") (pinfunction "SS_14") (pintype "bidirectional"))
    )
    (net (code "30") (name "Net-(C7-P$1)") (class "Default")
      (node (ref "C7") (pin "1") (pinfunction "P$1_1") (pintype "bidirectional"))
      (node (ref "U2") (pin "3") (pinfunction "BOOT1_3") (pintype "bidirectional"))
    )
    (net (code "31") (name "Net-(C8-P$1)") (class "Default")
      (node (ref "C8") (pin "1") (pinfunction "P$1_1") (pintype "bidirectional"))
      (node (ref "U2") (pin "17") (pinfunction "BOOT2_17") (pintype "bidirectional"))
    )
    (net (code "32") (name "Net-(C9-P$1)") (class "Default")
      (node (ref "C9") (pin "1") (pinfunction "P$1_1") (pintype "bidirectional"))
      (node (ref "U2") (pin "6") (pinfunction "COMM1_6") (pintype "bidirectional"))
    )
    (net (code "33") (name "Net-(C10-P$1)") (class "Default")
      (node (ref "C10") (pin "1") (pinfunction "P$1_1") (pintype "bidirectional"))
      (node (ref "U2") (pin "15") (pinfunction "COMM2_15") (pintype "bidirectional"))
    )
    (net (code "34") (name "Net-(C10-P$2)") (class "Default")
      (node (ref "C10") (pin "2") (pinfunction "P$2_2") (pintype "bidirectional"))
      (node (ref "C12") (pin "2") (pinfunction "P$2_2") (pintype "bidirectional"))
      (node (ref "C5") (pin "2") (pinfunction "P$2_2") (pintype "bidirectional"))
      (node (ref "C8") (pin "2") (pinfunction "P$2_2") (pintype "bidirectional"))
      (node (ref "P1") (pin "2") (pinfunction "S_2") (pintype "passive"))
      (node (ref "U2") (pin "19") (pinfunction "AC2_19") (pintype "bidirectional"))
    )
    (net (code "35") (name "Net-(C11-P$1)") (class "Default")
      (node (ref "C11") (pin "1") (pinfunction "P$1_1") (pintype "bidirectional"))
      (node (ref "U2") (pin "5") (pinfunction "CLAMP1_5") (pintype "bidirectional"))
    )
    (net (code "36") (name "Net-(C11-P$2)") (class "Default")
      (node (ref "C11") (pin "2") (pinfunction "P$2_2") (pintype "bidirectional"))
      (node (ref "C3") (pin "1") (pinfunction "P$1_1") (pintype "bidirectional"))
      (node (ref "C5") (pin "1") (pinfunction "P$1_1") (pintype "bidirectional"))
      (node (ref "C7") (pin "2") (pinfunction "P$2_2") (pintype "bidirectional"))
      (node (ref "C9") (pin "2") (pinfunction "P$2_2") (pintype "bidirectional"))
      (node (ref "U2") (pin "2") (pinfunction "AC1_2") (pintype "bidirectional"))
    )
    (net (code "37") (name "Net-(C12-P$1)") (class "Default")
      (node (ref "C12") (pin "1") (pinfunction "P$1_1") (pintype "bidirectional"))
      (node (ref "U2") (pin "16") (pinfunction "CLAMP2_16") (pintype "bidirectional"))
    )
    (net (code "38") (name "Net-(C13-P$1)") (class "Default")
      (node (ref "C13") (pin "1") (pinfunction "P$1_1") (pintype "bidirectional"))
      (node (ref "U1") (pin "13") (pinfunction "SS_13") (pintype "bidirectional"))
    )
    (net (code "39") (name "Net-(C20-P$1)") (class "Default")
      (node (ref "C20") (pin "1") (pinfunction "P$1_1") (pintype "bidirectional"))
      (node (ref "R17") (pin "1") (pinfunction "P$1_1") (pintype "bidirectional"))
      (node (ref "U3") (pin "3") (pinfunction "VDD_3") (pintype "bidirectional"))
    )
    (net (code "40") (name "Net-(C22-P$1)") (class "Default")
      (node (ref "C22") (pin "1") (pinfunction "P$1_1") (pintype "bidirectional"))
      (node (ref "C24") (pin "2") (pinfunction "P$2_2") (pintype "bidirectional"))
      (node (ref "E1") (pin "ANT") (pinfunction "SIGNAL_ANT") (pintype "bidirectional"))
    )
    (net (code "41") (name "Net-(C24-P$1)") (class "Default")
      (node (ref "C24") (pin "1") (pinfunction "P$1_1") (pintype "bidirectional"))
      (node (ref "C26") (pin "3") (pinfunction "O2_3") (pintype "bidirectional"))
    )
    (net (code "42") (name "Net-(C26-I)") (class "Default")
      (node (ref "C26") (pin "1") (pinfunction "I_1") (pintype "bidirectional"))
      (node (ref "L4") (pin "1") (pinfunction "P$1_1") (pintype "bidirectional"))
    )
    (net (code "43") (name "Net-(C30-P$1)") (class "Default")
      (node (ref "C30") (pin "1") (pinfunction "P$1_1") (pintype "bidirectional"))
      (node (ref "L4") (pin "2") (pinfunction "P$2_2") (pintype "bidirectional"))
      (node (ref "L5") (pin "1") (pinfunction "P$1_1") (pintype "bidirectional"))
    )
    (net (code "44") (name "Net-(C33-P$1)") (class "Default")
      (node (ref "C33") (pin "1") (pinfunction "P$1_1") (pintype "bidirectional"))
      (node (ref "L5") (pin "2") (pinfunction "P$2_2") (pintype "bidirectional"))
      (node (ref "L6") (pin "1") (pinfunction "P$1_1") (pintype "bidirectional"))
    )
    (net (code "45") (name "Net-(C33-P$2)") (class "Default")
      (node (ref "C33") (pin "2") (pinfunction "P$2_2") (pintype "bidirectional"))
      (node (ref "L7") (pin "2") (pinfunction "P$2_2") (pintype "bidirectional"))
      (node (ref "U5") (pin "1") (pinfunction "RF_P_1") (pintype "bidirectional"))
    )
    (net (code "46") (name "Net-(C34-P$2)") (class "Default")
      (node (ref "C34") (pin "2") (pinfunction "P$2_2") (pintype "bidirectional"))
      (node (ref "L6") (pin "2") (pinfunction "P$2_2") (pintype "bidirectional"))
      (node (ref "U5") (pin "2") (pinfunction "RF_N_2") (pintype "bidirectional"))
    )
    (net (code "47") (name "Net-(C35-P$1)") (class "Default")
      (node (ref "C35") (pin "1") (pinfunction "P$1_1") (pintype "bidirectional"))
      (node (ref "L7") (pin "1") (pinfunction "P$1_1") (pintype "bidirectional"))
    )
    (net (code "48") (name "Net-(C45-P$1)") (class "Default")
      (node (ref "C45") (pin "1") (pinfunction "P$1_1") (pintype "bidirectional"))
      (node (ref "U8") (pin "10") (pinfunction "REGOUT_10") (pintype "bidirectional"))
    )
    (net (code "49") (name "Net-(C48-P$1)") (class "Default")
      (node (ref "C48") (pin "1") (pinfunction "P$1_1") (pintype "bidirectional"))
      (node (ref "R28") (pin "1") (pinfunction "P$1_1") (pintype "bidirectional"))
      (node (ref "U9") (pin "7") (pinfunction "VREF2_7") (pintype "bidirectional"))
      (node (ref "U9") (pin "8") (pinfunction "EN_8") (pintype "bidirectional"))
    )
    (net (code "50") (name "Net-(JP3-Pad2)") (class "Default")
      (node (ref "JP3") (pin "2") (pinfunction "2_2") (pintype "passive"))
      (node (ref "U1") (pin "15") (pinfunction "PG_15") (pintype "bidirectional"))
    )
    (net (code "51") (name "Net-(L1-P$2)") (class "Default")
      (node (ref "L1") (pin "2") (pinfunction "P$2_2") (pintype "bidirectional"))
      (node (ref "U1") (pin "3") (pinfunction "SW_3") (pintype "bidirectional"))
    )
    (net (code "52") (name "Net-(L2-P$2)") (class "Default")
      (node (ref "L2") (pin "2") (pinfunction "P$2_2") (pintype "bidirectional"))
      (node (ref "U1") (pin "4") (pinfunction "SW_4") (pintype "bidirectional"))
    )
    (net (code "53") (name "Net-(P2B-S)") (class "Default")
      (node (ref "F1") (pin "1") (pinfunction "1_1") (pintype "passive"))
      (node (ref "P2") (pin "2") (pinfunction "S_2") (pintype "passive"))
    )
    (net (code "54") (name "Net-(P3A-S)") (class "Default")
      (node (ref "P3") (pin "1") (pinfunction "S_1") (pintype "passive"))
      (node (ref "U10") (pin "7") (pinfunction "OUT+_7") (pintype "bidirectional"))
    )
    (net (code "55") (name "Net-(P3B-S)") (class "Default")
      (node (ref "P3") (pin "2") (pinfunction "S_2") (pintype "passive"))
      (node (ref "U10") (pin "9") (pinfunction "OUT-_9") (pintype "bidirectional"))
    )
    (net (code "56") (name "Net-(P4A-S)") (class "Default")
      (node (ref "P4") (pin "1") (pinfunction "S_1") (pintype "passive"))
      (node (ref "U11") (pin "7") (pinfunction "OUT+_7") (pintype "bidirectional"))
    )
    (net (code "57") (name "Net-(P4B-S)") (class "Default")
      (node (ref "P4") (pin "2") (pinfunction "S_2") (pintype "passive"))
      (node (ref "U11") (pin "9") (pinfunction "OUT-_9") (pintype "bidirectional"))
    )
    (net (code "58") (name "Net-(R2-P$1)") (class "Default")
      (node (ref "R2") (pin "1") (pinfunction "P$1_1") (pintype "bidirectional"))
      (node (ref "R3") (pin "2") (pinfunction "P$2_2") (pintype "bidirectional"))
      (node (ref "U1") (pin "16") (pinfunction "FB_16") (pintype "bidirectional"))
    )
    (net (code "59") (name "Net-(R4-P$1)") (class "Default")
      (node (ref "R4") (pin "1") (pinfunction "P$1_1") (pintype "bidirectional"))
      (node (ref "U1") (pin "18") (pinfunction "EN_18") (pintype "bidirectional"))
    )
    (net (code "60") (name "Net-(R5-P$1)") (class "Default")
      (node (ref "R5") (pin "1") (pinfunction "P$1_1") (pintype "bidirectional"))
      (node (ref "U1") (pin "9") (pinfunction "EN_9") (pintype "bidirectional"))
    )
    (net (code "61") (name "Net-(R7-P$2)") (class "Default")
      (node (ref "R7") (pin "2") (pinfunction "P$2_2") (pintype "bidirectional"))
      (node (ref "R8") (pin "1") (pinfunction "P$1_1") (pintype "bidirectional"))
      (node (ref "U1") (pin "11") (pinfunction "FB_11") (pintype "bidirectional"))
    )
    (net (code "62") (name "Net-(R9-P$2)") (class "Default")
      (node (ref "R9") (pin "2") (pinfunction "P$2_2") (pintype "bidirectional"))
      (node (ref "U2") (pin "10") (pinfunction "TERM_10") (pintype "bidirectional"))
    )
    (net (code "63") (name "Net-(R11-P$1)") (class "Default")
      (node (ref "R11") (pin "1") (pinfunction "P$1_1") (pintype "bidirectional"))
      (node (ref "U2") (pin "12") (pinfunction "ILIM_12") (pintype "bidirectional"))
    )
    (net (code "64") (name "Net-(R11-P$2)") (class "Default")
      (node (ref "R11") (pin "2") (pinfunction "P$2_2") (pintype "bidirectional"))
      (node (ref "R12") (pin "2") (pinfunction "P$2_2") (pintype "bidirectional"))
      (node (ref "R13") (pin "1") (pinfunction "P$1_1") (pintype "bidirectional"))
      (node (ref "U2") (pin "14") (pinfunction "FOD_14") (pintype "bidirectional"))
    )
    (net (code "65") (name "Net-(R13-P$2)") (class "Default")
      (node (ref "C17") (pin "P$1") (pinfunction "P$1_P$1") (pintype "bidirectional"))
      (node (ref "R13") (pin "2") (pinfunction "P$2_2") (pintype "bidirectional"))
      (node (ref "U2") (pin "18") (pinfunction "RECT_18") (pintype "bidirectional"))
    )
    (net (code "66") (name "Net-(R18-P$2)") (class "Default")
      (node (ref "R18") (pin "2") (pinfunction "P$2_2") (pintype "bidirectional"))
      (node (ref "U3") (pin "5") (pinfunction "VM_5") (pintype "bidirectional"))
    )
    (net (code "67") (name "Net-(R24-P$1)") (class "Default")
      (node (ref "R24") (pin "1") (pinfunction "P$1_1") (pintype "bidirectional"))
      (node (ref "U6") (pin "3") (pinfunction "~{WP}/IO2_3") (pintype "input"))
    )
    (net (code "68") (name "Net-(R25-P$1)") (class "Default")
      (node (ref "R25") (pin "1") (pinfunction "P$1_1") (pintype "bidirectional"))
      (node (ref "U6") (pin "7") (pinfunction "~{HOLD}/IO3_7") (pintype "input"))
    )
    (net (code "69") (name "Net-(R26-P$1)") (class "Default")
      (node (ref "R26") (pin "1") (pinfunction "P$1_1") (pintype "bidirectional"))
      (node (ref "U8") (pin "23") (pinfunction "SCL_23") (pintype "bidirectional"))
      (node (ref "U9") (pin "3") (pinfunction "SCL1_3") (pintype "bidirectional"))
    )
    (net (code "70") (name "Net-(R27-P$1)") (class "Default")
      (node (ref "R27") (pin "1") (pinfunction "P$1_1") (pintype "bidirectional"))
      (node (ref "U8") (pin "24") (pinfunction "SDI_24") (pintype "bidirectional"))
      (node (ref "U9") (pin "4") (pinfunction "SDA1_4") (pintype "bidirectional"))
    )
    (net (code "71") (name "Net-(TC1F-S)") (class "Default")
      (node (ref "JP2") (pin "2") (pinfunction "2_2") (pintype "passive"))
      (node (ref "TC1") (pin "5") (pinfunction "S_5") (pintype "passive"))
    )
    (net (code "72") (name "Net-(TC1H-S)") (class "Default")
      (node (ref "JP1") (pin "2") (pinfunction "2_2") (pintype "passive"))
      (node (ref "TC1") (pin "7") (pinfunction "S_7") (pintype "passive"))
    )
    (net (code "73") (name "Net-(U5-DCOUPL)") (class "Default")
      (node (ref "C39") (pin "P$1") (pinfunction "P$1_P$1") (pintype "bidirectional"))
      (node (ref "U5") (pin "23") (pinfunction "DCOUPL_23") (pintype "bidirectional"))
    )
    (net (code "74") (name "Net-(U7A-A)") (class "Default")
      (node (ref "U7") (pin "2") (pinfunction "A_2") (pintype "input"))
      (node (ref "U8") (pin "12") (pinfunction "INT_12") (pintype "bidirectional"))
    )
    (net (code "75") (name "Net-(U10-REG)") (class "Default")
      (node (ref "C50") (pin "P$1") (pinfunction "P$1_P$1") (pintype "bidirectional"))
      (node (ref "U10") (pin "1") (pinfunction "REG_1") (pintype "bidirectional"))
    )
    (net (code "76") (name "Net-(U11-REG)") (class "Default")
      (node (ref "C54") (pin "P$1") (pinfunction "P$1_P$1") (pintype "bidirectional"))
      (node (ref "U11") (pin "1") (pinfunction "REG_1") (pintype "bidirectional"))
    )
    (net (code "77") (name "Net-(U12-VCAP)") (class "Default")
      (node (ref "C60") (pin "P$1") (pinfunction "P$1_P$1") (pintype "bidirectional"))
      (node (ref "U12") (pin "7") (pinfunction "VCAP_7") (pintype "bidirectional"))
    )
    (net (code "78") (name "PCAP_RX0") (class "Default")
      (node (ref "MAT-X1") (pin "P$2") (pinfunction "1_P$2") (pintype "bidirectional"))
      (node (ref "U12") (pin "27") (pinfunction "RX0_27") (pintype "bidirectional"))
    )
    (net (code "79") (name "PCAP_RX1") (class "Default")
      (node (ref "MAT-X2") (pin "P$2") (pinfunction "1_P$2") (pintype "bidirectional"))
      (node (ref "U12") (pin "26") (pinfunction "RX1_26") (pintype "bidirectional"))
    )
    (net (code "80") (name "PCAP_RX2") (class "Default")
      (node (ref "MAT-X3") (pin "P$2") (pinfunction "1_P$2") (pintype "bidirectional"))
      (node (ref "U12") (pin "25") (pinfunction "RX2_25") (pintype "bidirectional"))
    )
    (net (code "81") (name "PCAP_RX3") (class "Default")
      (node (ref "MAT-X4") (pin "P$2") (pinfunction "1_P$2") (pintype "bidirectional"))
      (node (ref "U12") (pin "24") (pinfunction "RX3_24") (pintype "bidirectional"))
    )
    (net (code "82") (name "PCAP_RX4") (class "Default")
      (node (ref "MAT-Y1") (pin "P$2") (pinfunction "1_P$2") (pintype "bidirectional"))
      (node (ref "MAT-Y1") (pin "P$3") (pinfunction "1_P$3") (pintype "bidirectional"))
      (node (ref "MAT-Y1") (pin "P$4") (pinfunction "1_P$4") (pintype "bidirectional"))
      (node (ref "MAT-Y1") (pin "P$5") (pinfunction "1_P$5") (pintype "bidirectional"))
      (node (ref "MAT-Y1") (pin "P$8") (pinfunction "1_P$8") (pintype "bidirectional"))
      (node (ref "U12") (pin "23") (pinfunction "RX4_23") (pintype "bidirectional"))
    )
    (net (code "83") (name "PCAP_RX5") (class "Default")
      (node (ref "MAT-Y2") (pin "P$2") (pinfunction "1_P$2") (pintype "bidirectional"))
      (node (ref "MAT-Y2") (pin "P$3") (pinfunction "1_P$3") (pintype "bidirectional"))
      (node (ref "MAT-Y2") (pin "P$4") (pinfunction "1_P$4") (pintype "bidirectional"))
      (node (ref "MAT-Y2") (pin "P$5") (pinfunction "1_P$5") (pintype "bidirectional"))
      (node (ref "MAT-Y2") (pin "P$8") (pinfunction "1_P$8") (pintype "bidirectional"))
      (node (ref "U12") (pin "22") (pinfunction "RX5_22") (pintype "bidirectional"))
    )
    (net (code "84") (name "PCAP_RX6") (class "Default")
      (node (ref "MAT-Y3") (pin "P$2") (pinfunction "1_P$2") (pintype "bidirectional"))
      (node (ref "MAT-Y3") (pin "P$3") (pinfunction "1_P$3") (pintype "bidirectional"))
      (node (ref "MAT-Y3") (pin "P$4") (pinfunction "1_P$4") (pintype "bidirectional"))
      (node (ref "MAT-Y3") (pin "P$5") (pinfunction "1_P$5") (pintype "bidirectional"))
      (node (ref "MAT-Y3") (pin "P$8") (pinfunction "1_P$8") (pintype "bidirectional"))
      (node (ref "U12") (pin "21") (pinfunction "RX6_21") (pintype "bidirectional"))
    )
    (net (code "85") (name "PCAP_RX7") (class "Default")
      (node (ref "MAT-Y4") (pin "P$2") (pinfunction "1_P$2") (pintype "bidirectional"))
      (node (ref "MAT-Y4") (pin "P$3") (pinfunction "1_P$3") (pintype "bidirectional"))
      (node (ref "MAT-Y4") (pin "P$4") (pinfunction "1_P$4") (pintype "bidirectional"))
      (node (ref "MAT-Y4") (pin "P$5") (pinfunction "1_P$5") (pintype "bidirectional"))
      (node (ref "MAT-Y4") (pin "P$8") (pinfunction "1_P$8") (pintype "bidirectional"))
      (node (ref "U12") (pin "20") (pinfunction "RX7_20") (pintype "bidirectional"))
    )
    (net (code "86") (name "PCAP_RX8") (class "Default")
      (node (ref "MAT-Y5") (pin "P$2") (pinfunction "1_P$2") (pintype "bidirectional"))
      (node (ref "MAT-Y5") (pin "P$3") (pinfunction "1_P$3") (pintype "bidirectional"))
      (node (ref "MAT-Y5") (pin "P$4") (pinfunction "1_P$4") (pintype "bidirectional"))
      (node (ref "MAT-Y5") (pin "P$5") (pinfunction "1_P$5") (pintype "bidirectional"))
      (node (ref "MAT-Y5") (pin "P$8") (pinfunction "1_P$8") (pintype "bidirectional"))
      (node (ref "U12") (pin "19") (pinfunction "RX8_19") (pintype "bidirectional"))
    )
    (net (code "87") (name "PCAP_TX0") (class "Default")
      (node (ref "MAT-Y9") (pin "P$2") (pinfunction "1_P$2") (pintype "bidirectional"))
      (node (ref "MAT-Y9") (pin "P$3") (pinfunction "1_P$3") (pintype "bidirectional"))
      (node (ref "MAT-Y9") (pin "P$4") (pinfunction "1_P$4") (pintype "bidirectional"))
      (node (ref "MAT-Y9") (pin "P$5") (pinfunction "1_P$5") (pintype "bidirectional"))
      (node (ref "MAT-Y9") (pin "P$8") (pinfunction "1_P$8") (pintype "bidirectional"))
      (node (ref "U12") (pin "33") (pinfunction "TX0_33") (pintype "bidirectional"))
    )
    (net (code "88") (name "PCAP_TX1") (class "Default")
      (node (ref "MAT-Y8") (pin "P$2") (pinfunction "1_P$2") (pintype "bidirectional"))
      (node (ref "MAT-Y8") (pin "P$3") (pinfunction "1_P$3") (pintype "bidirectional"))
      (node (ref "MAT-Y8") (pin "P$4") (pinfunction "1_P$4") (pintype "bidirectional"))
      (node (ref "MAT-Y8") (pin "P$5") (pinfunction "1_P$5") (pintype "bidirectional"))
      (node (ref "MAT-Y8") (pin "P$8") (pinfunction "1_P$8") (pintype "bidirectional"))
      (node (ref "U12") (pin "32") (pinfunction "TX1_32") (pintype "bidirectional"))
    )
    (net (code "89") (name "PCAP_TX2") (class "Default")
      (node (ref "MAT-Y7") (pin "P$2") (pinfunction "1_P$2") (pintype "bidirectional"))
      (node (ref "MAT-Y7") (pin "P$3") (pinfunction "1_P$3") (pintype "bidirectional"))
      (node (ref "MAT-Y7") (pin "P$4") (pinfunction "1_P$4") (pintype "bidirectional"))
      (node (ref "MAT-Y7") (pin "P$5") (pinfunction "1_P$5") (pintype "bidirectional"))
      (node (ref "MAT-Y7") (pin "P$8") (pinfunction "1_P$8") (pintype "bidirectional"))
      (node (ref "U12") (pin "31") (pinfunction "TX2_31") (pintype "bidirectional"))
    )
    (net (code "90") (name "PCAP_TX3") (class "Default")
      (node (ref "MAT-Y6") (pin "P$2") (pinfunction "1_P$2") (pintype "bidirectional"))
      (node (ref "MAT-Y6") (pin "P$3") (pinfunction "1_P$3") (pintype "bidirectional"))
      (node (ref "MAT-Y6") (pin "P$4") (pinfunction "1_P$4") (pintype "bidirectional"))
      (node (ref "MAT-Y6") (pin "P$5") (pinfunction "1_P$5") (pintype "bidirectional"))
      (node (ref "MAT-Y6") (pin "P$8") (pinfunction "1_P$8") (pintype "bidirectional"))
      (node (ref "U12") (pin "30") (pinfunction "TX3_30") (pintype "bidirectional"))
    )
    (net (code "91") (name "QI_CTRL") (class "Default")
      (node (ref "R14") (pin "2") (pinfunction "P$2_2") (pintype "bidirectional"))
      (node (ref "U2") (pin "13") (pinfunction "TS/CTRL_13") (pintype "bidirectional"))
      (node (ref "U5") (pin "18") (pinfunction "DIO_12_18") (pintype "bidirectional"))
    )
    (net (code "92") (name "SCL") (class "Default")
      (node (ref "R22") (pin "1") (pinfunction "P$1_1") (pintype "bidirectional"))
      (node (ref "SCL") (pin "1") (pinfunction "S_1") (pintype "passive"))
      (node (ref "U10") (pin "2") (pinfunction "SCL_2") (pintype "bidirectional"))
      (node (ref "U11") (pin "2") (pinfunction "SCL_2") (pintype "bidirectional"))
      (node (ref "U12") (pin "44") (pinfunction "SCL_44") (pintype "bidirectional"))
      (node (ref "U5") (pin "15") (pinfunction "DIO_9_15") (pintype "bidirectional"))
      (node (ref "U9") (pin "6") (pinfunction "SCL2_6") (pintype "bidirectional"))
    )
    (net (code "93") (name "SDA") (class "Default")
      (node (ref "R23") (pin "1") (pinfunction "P$1_1") (pintype "bidirectional"))
      (node (ref "SDA") (pin "1") (pinfunction "S_1") (pintype "passive"))
      (node (ref "U10") (pin "3") (pinfunction "SDA_3") (pintype "bidirectional"))
      (node (ref "U11") (pin "3") (pinfunction "SDA_3") (pintype "bidirectional"))
      (node (ref "U12") (pin "1") (pinfunction "SDA_1") (pintype "bidirectional"))
      (node (ref "U5") (pin "16") (pinfunction "DIO_10_16") (pintype "bidirectional"))
      (node (ref "U9") (pin "5") (pinfunction "SDA2_5") (pintype "bidirectional"))
    )
    (net (code "94") (name "TC_INT") (class "Default")
      (node (ref "U12") (pin "8") (pinfunction "INT_8") (pintype "bidirectional"))
      (node (ref "U5") (pin "29") (pinfunction "DIO_19_29") (pintype "bidirectional"))
    )
    (net (code "95") (name "TC_~{RESET}") (class "Default")
      (node (ref "R37") (pin "1") (pinfunction "P$1_1") (pintype "bidirectional"))
      (node (ref "U12") (pin "18") (pinfunction "~{RESET}_18") (pintype "bidirectional"))
      (node (ref "U5") (pin "28") (pinfunction "DIO_18_28") (pintype "bidirectional"))
    )
    (net (code "96") (name "VBAT") (class "Default")
      (node (ref "C1") (pin "P$1") (pinfunction "P$1_P$1") (pintype "bidirectional"))
      (node (ref "C15") (pin "P$1") (pinfunction "P$1_P$1") (pintype "bidirectional"))
      (node (ref "C16") (pin "P$1") (pinfunction "P$1_P$1") (pintype "bidirectional"))
      (node (ref "C19") (pin "P$1") (pinfunction "P$1_P$1") (pintype "bidirectional"))
      (node (ref "C2") (pin "P$1") (pinfunction "P$1_P$1") (pintype "bidirectional"))
      (node (ref "C21") (pin "1") (pinfunction "P$1_1") (pintype "bidirectional"))
      (node (ref "C49") (pin "1") (pinfunction "P$1_1") (pintype "bidirectional"))
      (node (ref "C53") (pin "1") (pinfunction "P$1_1") (pintype "bidirectional"))
      (node (ref "C62") (pin "P$1") (pinfunction "P$1_P$1") (pintype "bidirectional"))
      (node (ref "F1") (pin "2") (pinfunction "2_2") (pintype "passive"))
      (node (ref "R15") (pin "2") (pinfunction "P$2_2") (pintype "bidirectional"))
      (node (ref "R17") (pin "2") (pinfunction "P$2_2") (pintype "bidirectional"))
      (node (ref "R4") (pin "2") (pinfunction "P$2_2") (pintype "bidirectional"))
      (node (ref "R5") (pin "2") (pinfunction "P$2_2") (pintype "bidirectional"))
      (node (ref "U1") (pin "1") (pinfunction "VIN_1") (pintype "bidirectional"))
      (node (ref "U1") (pin "20") (pinfunction "AVIN_20") (pintype "bidirectional"))
      (node (ref "U1") (pin "6") (pinfunction "VIN_6") (pintype "bidirectional"))
      (node (ref "U1") (pin "7") (pinfunction "AVIN_7") (pintype "bidirectional"))
      (node (ref "U10") (pin "10") (pinfunction "VDD_10") (pintype "bidirectional"))
      (node (ref "U10") (pin "6") (pinfunction "VDD_6") (pintype "bidirectional"))
      (node (ref "U11") (pin "10") (pinfunction "VDD_10") (pintype "bidirectional"))
      (node (ref "U11") (pin "6") (pinfunction "VDD_6") (pintype "bidirectional"))
      (node (ref "U2") (pin "4") (pinfunction "BAT_4") (pintype "bidirectional"))
    )
    (net (code "97") (name "VBAT_SNS") (class "Default")
      (node (ref "C18") (pin "1") (pinfunction "P$1_1") (pintype "bidirectional"))
      (node (ref "R15") (pin "1") (pinfunction "P$1_1") (pintype "bidirectional"))
      (node (ref "R16") (pin "2") (pinfunction "P$2_2") (pintype "bidirectional"))
      (node (ref "U5") (pin "36") (pinfunction "DIO_23_36") (pintype "bidirectional"))
    )
    (net (code "98") (name "VDDR") (class "Default")
      (node (ref "C36") (pin "P$1") (pinfunction "P$1_P$1") (pintype "bidirectional"))
      (node (ref "C37") (pin "1") (pinfunction "P$1_1") (pintype "bidirectional"))
      (node (ref "C38") (pin "1") (pinfunction "P$1_1") (pintype "bidirectional"))
      (node (ref "L8") (pin "2") (pinfunction "P$2_2") (pintype "bidirectional"))
      (node (ref "U5") (pin "45") (pinfunction "VDDR_45") (pintype "bidirectional"))
      (node (ref "U5") (pin "48") (pinfunction "VDDR_RF_48") (pintype "bidirectional"))
    )
    (net (code "99") (name "VDDS") (class "Default")
      (node (ref "C27") (pin "1") (pinfunction "P$1_1") (pintype "bidirectional"))
      (node (ref "C28") (pin "1") (pinfunction "P$1_1") (pintype "bidirectional"))
      (node (ref "C29") (pin "1") (pinfunction "P$1_1") (pintype "bidirectional"))
      (node (ref "C31") (pin "P$1") (pinfunction "P$1_P$1") (pintype "bidirectional"))
      (node (ref "C32") (pin "1") (pinfunction "P$1_1") (pintype "bidirectional"))
      (node (ref "L3") (pin "2") (pinfunction "P$2_2") (pintype "bidirectional"))
      (node (ref "R20") (pin "2") (pinfunction "P$2_2") (pintype "bidirectional"))
      (node (ref "U5") (pin "13") (pinfunction "VDDS_13") (pintype "bidirectional"))
      (node (ref "U5") (pin "22") (pinfunction "VDDS_22") (pintype "bidirectional"))
      (node (ref "U5") (pin "34") (pinfunction "VDDS_DCDC_34") (pintype "bidirectional"))
      (node (ref "U5") (pin "44") (pinfunction "VDDS_44") (pintype "bidirectional"))
    )
    (net (code "100") (name "XTAL_32K_Q1") (class "Default")
      (node (ref "C43") (pin "1") (pinfunction "P$1_1") (pintype "bidirectional"))
      (node (ref "U5") (pin "3") (pinfunction "X32K_Q1_3") (pintype "bidirectional"))
      (node (ref "X2") (pin "2") (pinfunction "2_2") (pintype "passive"))
    )
    (net (code "101") (name "XTAL_32K_Q2") (class "Default")
      (node (ref "C42") (pin "1") (pinfunction "P$1_1") (pintype "bidirectional"))
      (node (ref "U5") (pin "4") (pinfunction "X32K_Q2_4") (pintype "bidirectional"))
      (node (ref "X2") (pin "1") (pinfunction "1_1") (pintype "passive"))
    )
    (net (code "102") (name "XTAL_48M_N") (class "Default")
      (node (ref "C44") (pin "1") (pinfunction "P$1_1") (pintype "bidirectional"))
      (node (ref "U5") (pin "46") (pinfunction "X48M_N_46") (pintype "bidirectional"))
      (node (ref "X1") (pin "3") (pinfunction "2_3") (pintype "passive"))
    )
    (net (code "103") (name "XTAL_48M_P") (class "Default")
      (node (ref "C41") (pin "1") (pinfunction "P$1_1") (pintype "bidirectional"))
      (node (ref "U5") (pin "47") (pinfunction "X48M_P_47") (pintype "bidirectional"))
      (node (ref "X1") (pin "1") (pinfunction "1_1") (pintype "passive"))
    )
    (net (code "104") (name "unconnected-(U2-EN2-Pad11)") (class "Default")
      (node (ref "U2") (pin "11") (pinfunction "EN2_11") (pintype "bidirectional"))
    )
    (net (code "105") (name "unconnected-(U2-~{AD_EN}-Pad8)") (class "Default")
      (node (ref "U2") (pin "8") (pinfunction "~{AD_EN}_8") (pintype "bidirectional"))
    )
    (net (code "106") (name "unconnected-(U5-DIO_0-Pad5)") (class "Default")
      (node (ref "U5") (pin "5") (pinfunction "DIO_0_5") (pintype "bidirectional"))
    )
    (net (code "107") (name "unconnected-(U5-DIO_1-Pad6)") (class "Default")
      (node (ref "U5") (pin "6") (pinfunction "DIO_1_6") (pintype "bidirectional"))
    )
    (net (code "108") (name "unconnected-(U5-DIO_2-Pad7)") (class "Default")
      (node (ref "U5") (pin "7") (pinfunction "DIO_2_7") (pintype "bidirectional"))
    )
    (net (code "109") (name "unconnected-(U5-DIO_3-Pad8)") (class "Default")
      (node (ref "U5") (pin "8") (pinfunction "DIO_3_8") (pintype "bidirectional"))
    )
    (net (code "110") (name "unconnected-(U5-DIO_14-Pad20)") (class "Default")
      (node (ref "U5") (pin "20") (pinfunction "DIO_14_20") (pintype "bidirectional"))
    )
    (net (code "111") (name "unconnected-(U5-DIO_15-Pad21)") (class "Default")
      (node (ref "U5") (pin "21") (pinfunction "DIO_15_21") (pintype "bidirectional"))
    )
    (net (code "112") (name "unconnected-(U8-AUX_CL-Pad7)") (class "Default")
      (node (ref "U8") (pin "7") (pinfunction "AUX_CL_7") (pintype "bidirectional"))
    )
    (net (code "113") (name "unconnected-(U8-AUX_DA-Pad21)") (class "Default")
      (node (ref "U8") (pin "21") (pinfunction "AUX_DA_21") (pintype "bidirectional"))
    )
    (net (code "114") (name "unconnected-(U8-FSYNC-Pad11)") (class "Default")
      (node (ref "U8") (pin "11") (pinfunction "FSYNC_11") (pintype "bidirectional"))
    )
    (net (code "115") (name "unconnected-(U8-~{CS}-Pad22)") (class "Default")
      (node (ref "U8") (pin "22") (pinfunction "~{CS}_22") (pintype "bidirectional"))
    )
    (net (code "116") (name "unconnected-(U12-RX9-Pad15)") (class "Default")
      (node (ref "U12") (pin "15") (pinfunction "RX9_15") (pintype "bidirectional"))
    )
    (net (code "117") (name "unconnected-(U12-RX10-Pad14)") (class "Default")
      (node (ref "U12") (pin "14") (pinfunction "RX10_14") (pintype "bidirectional"))
    )
    (net (code "118") (name "unconnected-(U12-RX11-Pad11)") (class "Default")
      (node (ref "U12") (pin "11") (pinfunction "RX11_11") (pintype "bidirectional"))
    )
    (net (code "119") (name "unconnected-(U12-RX12-Pad10)") (class "Default")
      (node (ref "U12") (pin "10") (pinfunction "RX12_10") (pintype "bidirectional"))
    )
    (net (code "120") (name "unconnected-(U12-TX4-Pad34)") (class "Default")
      (node (ref "U12") (pin "34") (pinfunction "TX4_34") (pintype "bidirectional"))
    )
    (net (code "121") (name "unconnected-(U12-TX5-Pad38)") (class "Default")
      (node (ref "U12") (pin "38") (pinfunction "TX5_38") (pintype "bidirectional"))
    )
    (net (code "122") (name "unconnected-(U12-TX6-Pad37)") (class "Default")
      (node (ref "U12") (pin "37") (pinfunction "TX6_37") (pintype "bidirectional"))
    )
    (net (code "123") (name "unconnected-(U12-TX7-Pad36)") (class "Default")
      (node (ref "U12") (pin "36") (pinfunction "TX7_36") (pintype "bidirectional"))
    )
    (net (code "124") (name "unconnected-(U12-TX8-Pad35)") (class "Default")
      (node (ref "U12") (pin "35") (pinfunction "TX8_35") (pintype "bidirectional"))
    )
    (net (code "125") (name "unconnected-(U12-TX9-Pad41)") (class "Default")
      (node (ref "U12") (pin "41") (pinfunction "TX9_41") (pintype "bidirectional"))
    )
    (net (code "126") (name "unconnected-(U12-TX10-Pad42)") (class "Default")
      (node (ref "U12") (pin "42") (pinfunction "TX10_42") (pintype "bidirectional"))
    )
    (net (code "127") (name "unconnected-(U12-TX11-Pad43)") (class "Default")
      (node (ref "U12") (pin "43") (pinfunction "TX11_43") (pintype "bidirectional"))
    )
    (net (code "128") (name "unconnected-(U12-TX12-Pad13)") (class "Default")
      (node (ref "U12") (pin "13") (pinfunction "TX12_13") (pintype "bidirectional"))
    )
    (net (code "129") (name "unconnected-(U12-TX13-Pad12)") (class "Default")
      (node (ref "U12") (pin "12") (pinfunction "TX13_12") (pintype "bidirectional"))
    )
    (net (code "130") (name "unconnected-(U12-TX14-Pad5)") (class "Default")
      (node (ref "U12") (pin "5") (pinfunction "TX14_5") (pintype "bidirectional"))
    )
    (net (code "131") (name "unconnected-(U12-TX15-Pad4)") (class "Default")
      (node (ref "U12") (pin "4") (pinfunction "TX15_4") (pintype "bidirectional"))
    )
    (net (code "132") (name "unconnected-(U12-TX16-Pad3)") (class "Default")
      (node (ref "U12") (pin "3") (pinfunction "TX16_3") (pintype "bidirectional"))
    )
    (net (code "133") (name "unconnected-(U12-TX17-Pad2)") (class "Default")
      (node (ref "U12") (pin "2") (pinfunction "TX17_2") (pintype "bidirectional"))
    )
    (net (code "134") (name "~{QI_CHG}") (class "Default")
      (node (ref "R10") (pin "1") (pinfunction "P$1_1") (pintype "bidirectional"))
      (node (ref "U2") (pin "7") (pinfunction "~{CHG}_7") (pintype "bidirectional"))
      (node (ref "U5") (pin "19") (pinfunction "DIO_13_19") (pintype "bidirectional"))
    )
  )
)
